# mcu_stm32f4.net
KiCad netlist of a schematic drawn in Altium Designer
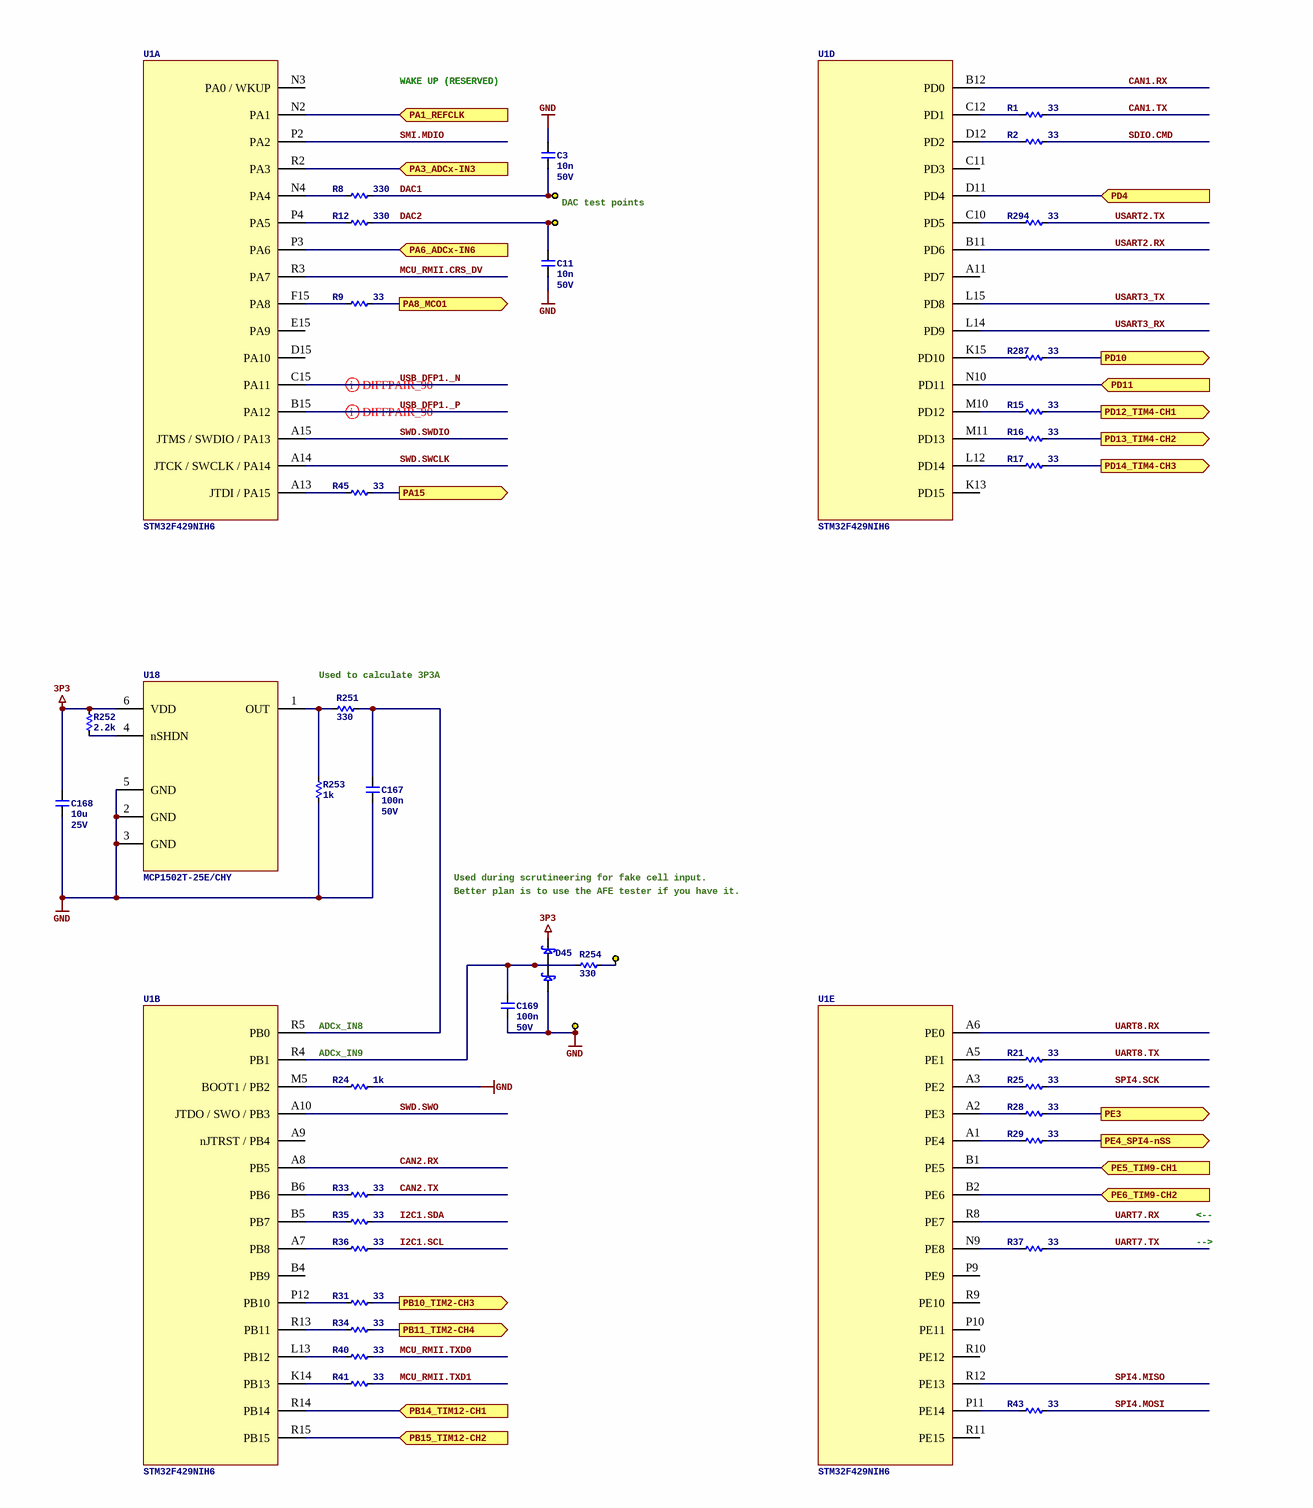
[diagram p0: mcu_stm32f4.SchDoc, top left]
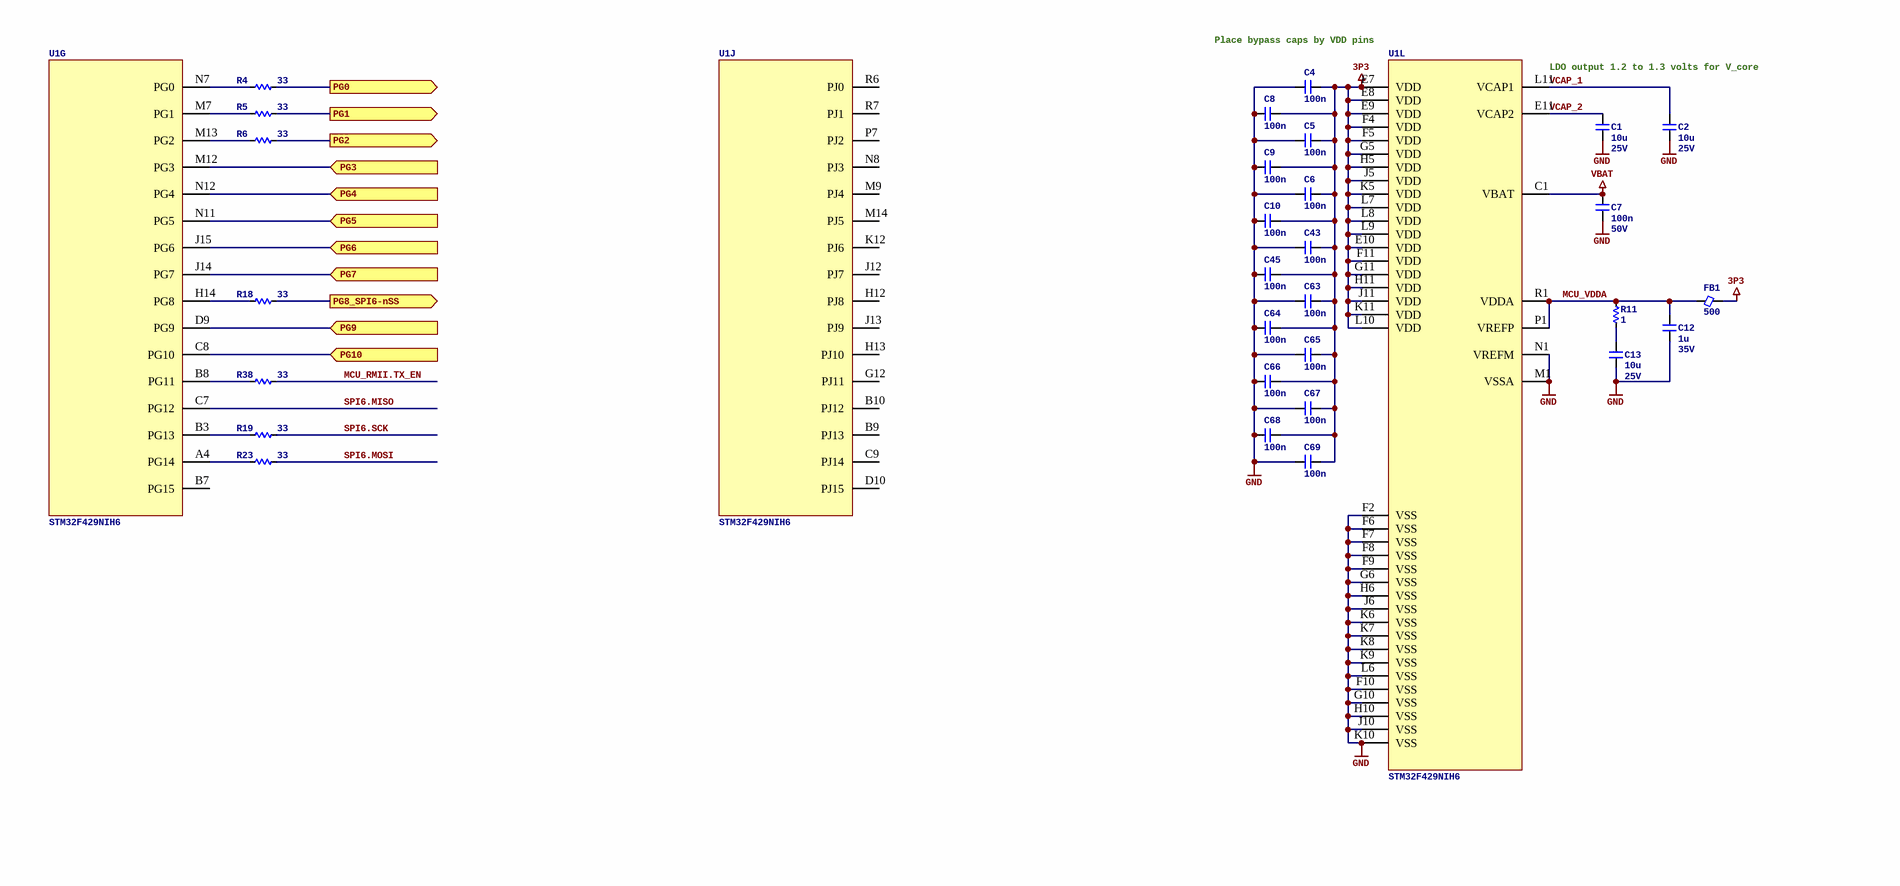
[diagram p1: mcu_stm32f4.SchDoc, top right]
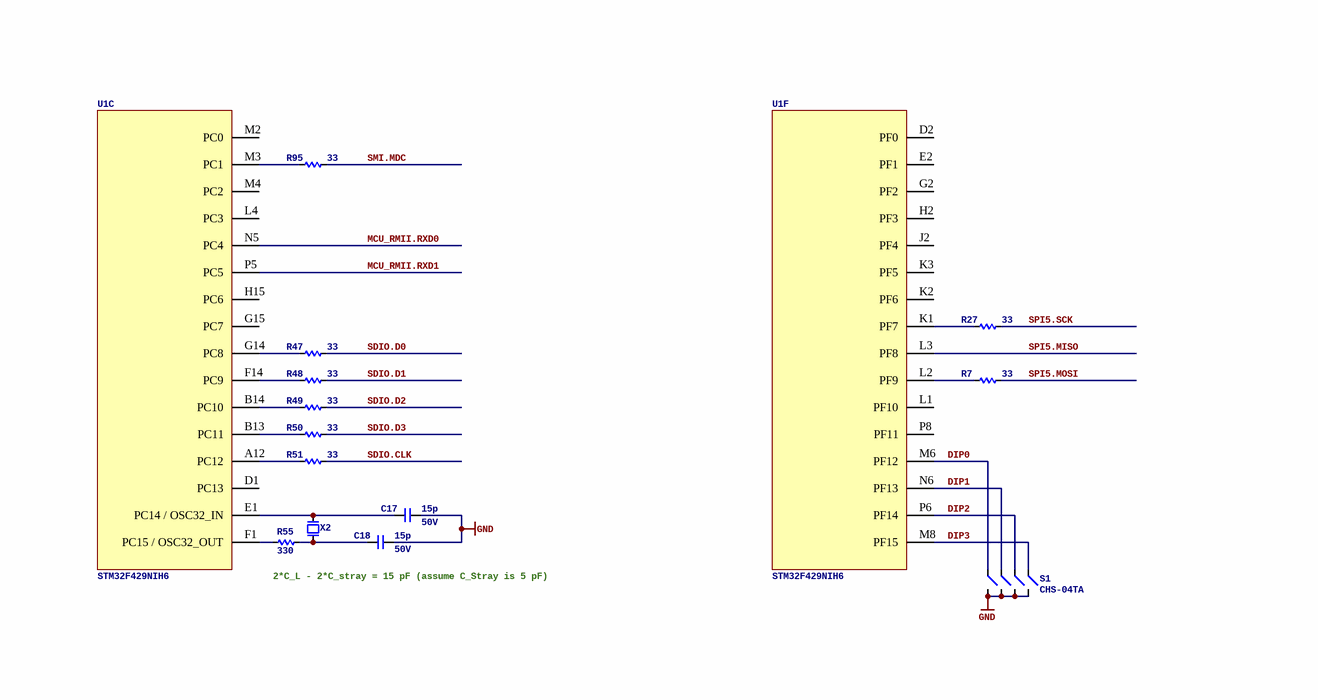
[diagram p2: mcu_stm32f4.SchDoc, bottom left]
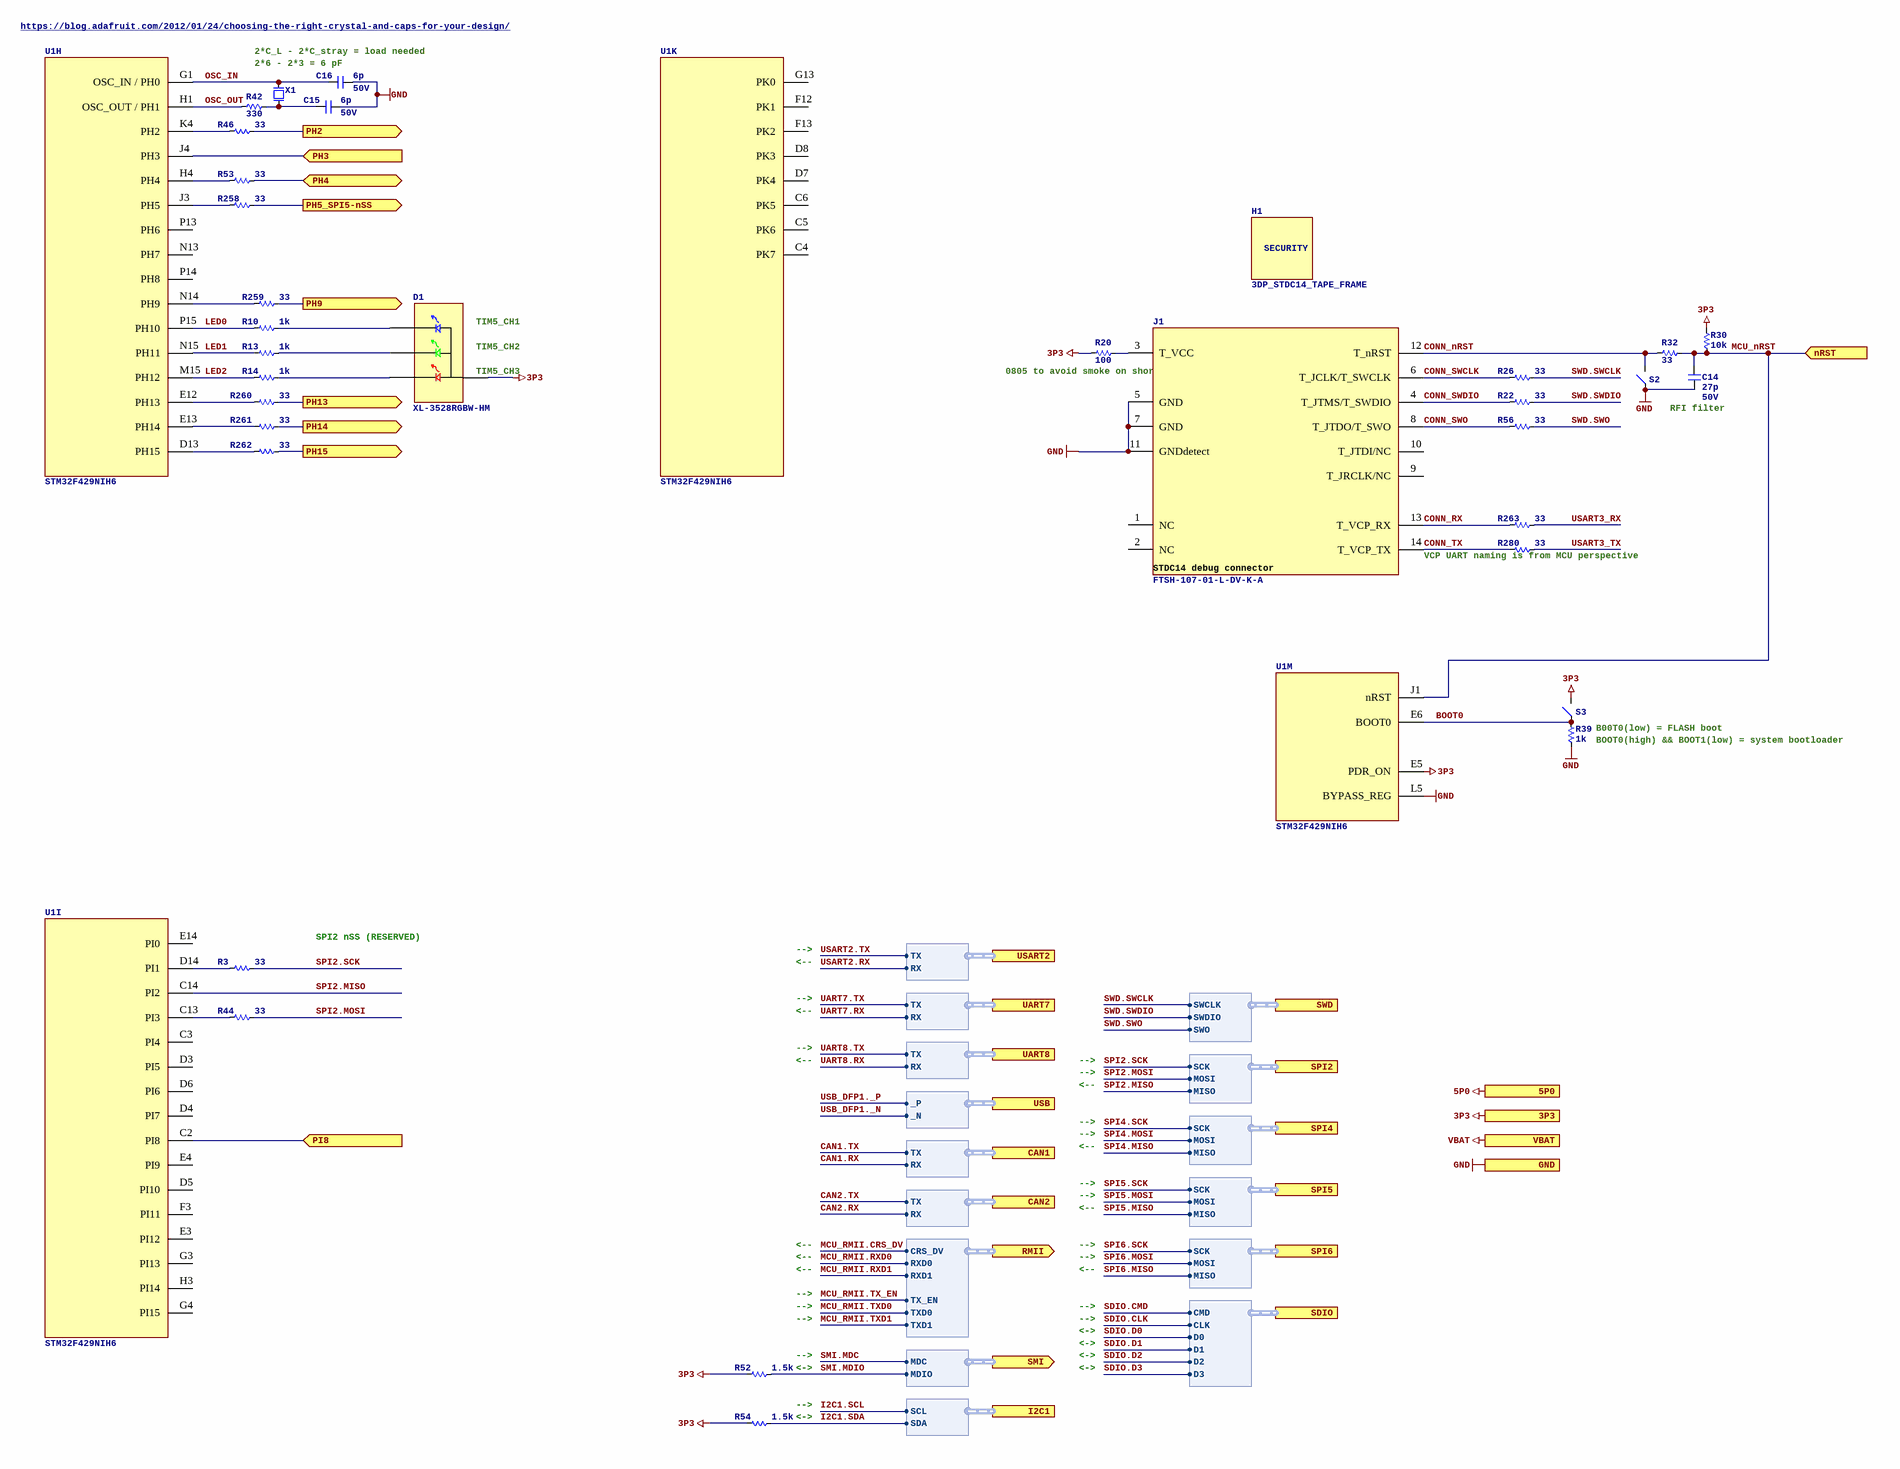
[diagram p3: mcu_stm32f4.SchDoc, bottom right]

(export (version "E")
  (design (tool "Eeschema 10.0.6"))
  (components
    (comp (ref "C1")
      (value "CL10A106MA8NRNC")
      (footprint "C0603")
      (fields
        (field (name "CAPACITANCE") "10u")
        (field (name "MANUFACTURER") "Samsung Electro-Mechanics")
        (field (name "VOLTAGE RATING") "25V")
      )
      (libsource (lib "database") (part "__template_cap"))
    )
    (comp (ref "C2")
      (value "CL10A106MA8NRNC")
      (footprint "C0603")
      (fields
        (field (name "CAPACITANCE") "10u")
        (field (name "MANUFACTURER") "Samsung Electro-Mechanics")
        (field (name "VOLTAGE RATING") "25V")
      )
      (libsource (lib "database") (part "__template_cap"))
    )
    (comp (ref "C3")
      (value "CL05B103KB5NNNC")
      (footprint "C0402")
      (fields
        (field (name "CAPACITANCE") "10n")
        (field (name "MANUFACTURER") "Samsung Electro-Mechanics")
        (field (name "VOLTAGE RATING") "50V")
      )
      (libsource (lib "database") (part "__template_cap"))
    )
    (comp (ref "C4")
      (value "CL05B104KB54PNC")
      (footprint "C0402")
      (fields (field (name "CAPACITANCE") "100n") (field (name "MANUFACTURER") "Samsung Electro-Mechanics"))
      (libsource (lib "database") (part "__template_cap"))
    )
    (comp (ref "C5")
      (value "CL05B104KB54PNC")
      (footprint "C0402")
      (fields (field (name "CAPACITANCE") "100n") (field (name "MANUFACTURER") "Samsung Electro-Mechanics"))
      (libsource (lib "database") (part "__template_cap"))
    )
    (comp (ref "C6")
      (value "CL05B104KB54PNC")
      (footprint "C0402")
      (fields (field (name "CAPACITANCE") "100n") (field (name "MANUFACTURER") "Samsung Electro-Mechanics"))
      (libsource (lib "database") (part "__template_cap"))
    )
    (comp (ref "C7")
      (value "CL05B104KB54PNC")
      (footprint "C0402")
      (fields
        (field (name "CAPACITANCE") "100n")
        (field (name "MANUFACTURER") "Samsung Electro-Mechanics")
        (field (name "VOLTAGE RATING") "50V")
      )
      (libsource (lib "database") (part "__template_cap"))
    )
    (comp (ref "C8")
      (value "CL05B104KB54PNC")
      (footprint "C0402")
      (fields (field (name "CAPACITANCE") "100n") (field (name "MANUFACTURER") "Samsung Electro-Mechanics"))
      (libsource (lib "database") (part "__template_cap"))
    )
    (comp (ref "C9")
      (value "CL05B104KB54PNC")
      (footprint "C0402")
      (fields (field (name "CAPACITANCE") "100n") (field (name "MANUFACTURER") "Samsung Electro-Mechanics"))
      (libsource (lib "database") (part "__template_cap"))
    )
    (comp (ref "C10")
      (value "CL05B104KB54PNC")
      (footprint "C0402")
      (fields (field (name "CAPACITANCE") "100n") (field (name "MANUFACTURER") "Samsung Electro-Mechanics"))
      (libsource (lib "database") (part "__template_cap"))
    )
    (comp (ref "C11")
      (value "CL05B103KB5NNNC")
      (footprint "C0402")
      (fields
        (field (name "CAPACITANCE") "10n")
        (field (name "MANUFACTURER") "Samsung Electro-Mechanics")
        (field (name "VOLTAGE RATING") "50V")
      )
      (libsource (lib "database") (part "__template_cap"))
    )
    (comp (ref "C12")
      (value "GMK107AB7105KAHT")
      (footprint "C0603")
      (fields
        (field (name "CAPACITANCE") "1u")
        (field (name "MANUFACTURER") "Taiyo Yuden")
        (field (name "VOLTAGE RATING") "35V")
      )
      (libsource (lib "database") (part "__template_cap"))
    )
    (comp (ref "C13")
      (value "CL21B106KAYQNNE")
      (footprint "C0805")
      (fields
        (field (name "CAPACITANCE") "10u")
        (field (name "MANUFACTURER") "Samsung Electro-Mechanics")
        (field (name "VOLTAGE RATING") "25V")
      )
      (libsource (lib "database") (part "__template_cap"))
    )
    (comp (ref "C14")
      (value "0402CG270J500NT")
      (footprint "C0402")
      (fields
        (field (name "CAPACITANCE") "27p")
        (field (name "MANUFACTURER") "FH(Guangdong Fenghua Advanced Tech)")
        (field (name "VOLTAGE RATING") "50V")
      )
      (libsource (lib "database") (part "__template_cap"))
    )
    (comp (ref "C15")
      (value "0402CG6R0C500NT")
      (footprint "C0402")
      (fields
        (field (name "CAPACITANCE") "6p")
        (field (name "MANUFACTURER") "FH(Guangdong Fenghua Advanced Tech)")
        (field (name "VOLTAGE RATING") "50V")
      )
      (libsource (lib "database") (part "__template_cap"))
    )
    (comp (ref "C16")
      (value "0402CG6R0C500NT")
      (footprint "C0402")
      (fields
        (field (name "CAPACITANCE") "6p")
        (field (name "MANUFACTURER") "FH(Guangdong Fenghua Advanced Tech)")
        (field (name "VOLTAGE RATING") "50V")
      )
      (libsource (lib "database") (part "__template_cap"))
    )
    (comp (ref "C17")
      (value "0402CG150J500NT")
      (footprint "C0402")
      (fields
        (field (name "CAPACITANCE") "15p")
        (field (name "MANUFACTURER") "FH(Guangdong Fenghua Advanced Tech)")
        (field (name "VOLTAGE RATING") "50V")
      )
      (libsource (lib "database") (part "__template_cap"))
    )
    (comp (ref "C18")
      (value "0402CG150J500NT")
      (footprint "C0402")
      (fields
        (field (name "CAPACITANCE") "15p")
        (field (name "MANUFACTURER") "FH(Guangdong Fenghua Advanced Tech)")
        (field (name "VOLTAGE RATING") "50V")
      )
      (libsource (lib "database") (part "__template_cap"))
    )
    (comp (ref "C43")
      (value "CL05B104KB54PNC")
      (footprint "C0402")
      (fields (field (name "CAPACITANCE") "100n") (field (name "MANUFACTURER") "Samsung Electro-Mechanics"))
      (libsource (lib "database") (part "__template_cap"))
    )
    (comp (ref "C45")
      (value "CL05B104KB54PNC")
      (footprint "C0402")
      (fields (field (name "CAPACITANCE") "100n") (field (name "MANUFACTURER") "Samsung Electro-Mechanics"))
      (libsource (lib "database") (part "__template_cap"))
    )
    (comp (ref "C63")
      (value "CL05B104KB54PNC")
      (footprint "C0402")
      (fields (field (name "CAPACITANCE") "100n") (field (name "MANUFACTURER") "Samsung Electro-Mechanics"))
      (libsource (lib "database") (part "__template_cap"))
    )
    (comp (ref "C64")
      (value "CL05B104KB54PNC")
      (footprint "C0402")
      (fields (field (name "CAPACITANCE") "100n") (field (name "MANUFACTURER") "Samsung Electro-Mechanics"))
      (libsource (lib "database") (part "__template_cap"))
    )
    (comp (ref "C65")
      (value "CL05B104KB54PNC")
      (footprint "C0402")
      (fields (field (name "CAPACITANCE") "100n") (field (name "MANUFACTURER") "Samsung Electro-Mechanics"))
      (libsource (lib "database") (part "__template_cap"))
    )
    (comp (ref "C66")
      (value "CL05B104KB54PNC")
      (footprint "C0402")
      (fields (field (name "CAPACITANCE") "100n") (field (name "MANUFACTURER") "Samsung Electro-Mechanics"))
      (libsource (lib "database") (part "__template_cap"))
    )
    (comp (ref "C67")
      (value "CL05B104KB54PNC")
      (footprint "C0402")
      (fields (field (name "CAPACITANCE") "100n") (field (name "MANUFACTURER") "Samsung Electro-Mechanics"))
      (libsource (lib "database") (part "__template_cap"))
    )
    (comp (ref "C68")
      (value "CL05B104KB54PNC")
      (footprint "C0402")
      (fields (field (name "CAPACITANCE") "100n") (field (name "MANUFACTURER") "Samsung Electro-Mechanics"))
      (libsource (lib "database") (part "__template_cap"))
    )
    (comp (ref "C69")
      (value "CL05B104KB54PNC")
      (footprint "C0402")
      (fields (field (name "CAPACITANCE") "100n") (field (name "MANUFACTURER") "Samsung Electro-Mechanics"))
      (libsource (lib "database") (part "__template_cap"))
    )
    (comp (ref "C167")
      (value "CL05B104KB54PNC")
      (footprint "C0402")
      (fields
        (field (name "CAPACITANCE") "100n")
        (field (name "MANUFACTURER") "Samsung Electro-Mechanics")
        (field (name "VOLTAGE RATING") "50V")
      )
      (libsource (lib "database") (part "__template_cap"))
    )
    (comp (ref "C168")
      (value "CL10A106MA8NRNC")
      (footprint "C0603")
      (fields
        (field (name "CAPACITANCE") "10u")
        (field (name "MANUFACTURER") "Samsung Electro-Mechanics")
        (field (name "VOLTAGE RATING") "25V")
      )
      (libsource (lib "database") (part "__template_cap"))
    )
    (comp (ref "C169")
      (value "CL05B104KB54PNC")
      (footprint "C0402")
      (fields
        (field (name "CAPACITANCE") "100n")
        (field (name "MANUFACTURER") "Samsung Electro-Mechanics")
        (field (name "VOLTAGE RATING") "50V")
      )
      (libsource (lib "database") (part "__template_cap"))
    )
    (comp (ref "D1")
      (value "XL-3528RGBW-HM")
      (footprint "LED_RGB_SMD3528-4P")
      (description "LED Multi-Color Chip Red/Green/Blue 621nm/525nm/468nm 25mA/15mA/15mA 4-Pin PLCC T/R")
      (fields (field (name "MANUFACTURER") "XINGLIGHT"))
      (libsource (lib "SSCP") (part "LED_RGB_XL-3528RGBW-HM"))
    )
    (comp (ref "D45")
      (value "BAT54SLT1G")
      (footprint "3SOT23")
      (description "DIODE SCHOTTKY DUAL 30V SOT23")
      (fields (field (name "MANUFACTURER") "ON Semiconductor"))
      (libsource (lib "SSCP") (part "SCHOTTKY_30V_DUAL_BAT54SLT1G"))
    )
    (comp (ref "FB1")
      (value "BLM15AX601SN1D")
      (footprint "FB0402")
      (fields (field (name "MANUFACTURER") "Murata Electronics") (field (name "CURRENT RATING (MA)") "500"))
      (libsource (lib "database") (part "__template_fb"))
    )
    (comp (ref "H1")
      (value "3DP_STDC14_TAPE_FRAME")
      (footprint "3DP_STDC14_TAPE_FRAME")
      (description "3D-printed plastic frame used for security tape around STDC14 programming header")
      (fields (field (name "MANUFACTURER") "SSCP"))
      (libsource (lib "SSCP") (part "3DP_STDC14_TAPE_FRAME"))
    )
    (comp (ref "J1")
      (value "FTSH-107-01-L-DV-K-A")
      (footprint "SAMTEC_FTSH-107-01-L-DV-K-A")
      (description "Connector Header Surface Mount 14 position 0.050\" (1.27mm)")
      (fields (field (name "MANUFACTURER") "Samtec"))
      (libsource (lib "SSCP") (part "CONN_14POS_50MIL_ST_CORTEX_DEBUG_VCP"))
    )
    (comp (ref "R1")
      (value "33")
      (footprint "R0402")
      (fields
        (field (name "TOLERANCE") "1%")
        (field (name "MANUFACTURER PART NUMBER") "0402WGF330JTCE")
        (field (name "MANUFACTURER") "UNI-ROYAL(Uniroyal Elec)")
      )
      (libsource (lib "database") (part "__template_resistor"))
    )
    (comp (ref "R2")
      (value "33")
      (footprint "R0402")
      (fields
        (field (name "TOLERANCE") "1%")
        (field (name "MANUFACTURER PART NUMBER") "0402WGF330JTCE")
        (field (name "MANUFACTURER") "UNI-ROYAL(Uniroyal Elec)")
      )
      (libsource (lib "database") (part "__template_resistor"))
    )
    (comp (ref "R3")
      (value "33")
      (footprint "R0402")
      (fields
        (field (name "TOLERANCE") "1%")
        (field (name "MANUFACTURER PART NUMBER") "0402WGF330JTCE")
        (field (name "MANUFACTURER") "UNI-ROYAL(Uniroyal Elec)")
      )
      (libsource (lib "database") (part "__template_resistor"))
    )
    (comp (ref "R4")
      (value "33")
      (footprint "R0402")
      (fields
        (field (name "TOLERANCE") "1%")
        (field (name "MANUFACTURER PART NUMBER") "0402WGF330JTCE")
        (field (name "MANUFACTURER") "UNI-ROYAL(Uniroyal Elec)")
      )
      (libsource (lib "database") (part "__template_resistor"))
    )
    (comp (ref "R5")
      (value "33")
      (footprint "R0402")
      (fields
        (field (name "TOLERANCE") "1%")
        (field (name "MANUFACTURER PART NUMBER") "0402WGF330JTCE")
        (field (name "MANUFACTURER") "UNI-ROYAL(Uniroyal Elec)")
      )
      (libsource (lib "database") (part "__template_resistor"))
    )
    (comp (ref "R6")
      (value "33")
      (footprint "R0402")
      (fields
        (field (name "TOLERANCE") "1%")
        (field (name "MANUFACTURER PART NUMBER") "0402WGF330JTCE")
        (field (name "MANUFACTURER") "UNI-ROYAL(Uniroyal Elec)")
      )
      (libsource (lib "database") (part "__template_resistor"))
    )
    (comp (ref "R7")
      (value "33")
      (footprint "R0402")
      (fields
        (field (name "TOLERANCE") "1%")
        (field (name "MANUFACTURER PART NUMBER") "0402WGF330JTCE")
        (field (name "MANUFACTURER") "UNI-ROYAL(Uniroyal Elec)")
      )
      (libsource (lib "database") (part "__template_resistor"))
    )
    (comp (ref "R8")
      (value "330")
      (footprint "R0402")
      (fields
        (field (name "TOLERANCE") "1%")
        (field (name "MANUFACTURER PART NUMBER") "0402WGF3300TCE")
        (field (name "MANUFACTURER") "UNI-ROYAL(Uniroyal Elec)")
      )
      (libsource (lib "database") (part "__template_resistor"))
    )
    (comp (ref "R9")
      (value "33")
      (footprint "R0402")
      (fields
        (field (name "TOLERANCE") "1%")
        (field (name "MANUFACTURER PART NUMBER") "0402WGF330JTCE")
        (field (name "MANUFACTURER") "UNI-ROYAL(Uniroyal Elec)")
      )
      (libsource (lib "database") (part "__template_resistor"))
    )
    (comp (ref "R10")
      (value "1k")
      (footprint "R0402")
      (fields
        (field (name "TOLERANCE") "1%")
        (field (name "MANUFACTURER PART NUMBER") "0402WGF1001TCE")
        (field (name "MANUFACTURER") "UNI-ROYAL(Uniroyal Elec)")
      )
      (libsource (lib "database") (part "__template_resistor"))
    )
    (comp (ref "R11")
      (value "1")
      (footprint "R0402")
      (fields
        (field (name "TOLERANCE") "1%")
        (field (name "MANUFACTURER PART NUMBER") "CRCW04021R00FKED")
        (field (name "MANUFACTURER") "Vishay Intertech")
      )
      (libsource (lib "database") (part "__template_resistor"))
    )
    (comp (ref "R12")
      (value "330")
      (footprint "R0402")
      (fields
        (field (name "TOLERANCE") "1%")
        (field (name "MANUFACTURER PART NUMBER") "0402WGF3300TCE")
        (field (name "MANUFACTURER") "UNI-ROYAL(Uniroyal Elec)")
      )
      (libsource (lib "database") (part "__template_resistor"))
    )
    (comp (ref "R13")
      (value "1k")
      (footprint "R0402")
      (fields
        (field (name "TOLERANCE") "1%")
        (field (name "MANUFACTURER PART NUMBER") "0402WGF1001TCE")
        (field (name "MANUFACTURER") "UNI-ROYAL(Uniroyal Elec)")
      )
      (libsource (lib "database") (part "__template_resistor"))
    )
    (comp (ref "R14")
      (value "1k")
      (footprint "R0402")
      (fields
        (field (name "TOLERANCE") "1%")
        (field (name "MANUFACTURER PART NUMBER") "0402WGF1001TCE")
        (field (name "MANUFACTURER") "UNI-ROYAL(Uniroyal Elec)")
      )
      (libsource (lib "database") (part "__template_resistor"))
    )
    (comp (ref "R15")
      (value "33")
      (footprint "R0402")
      (fields
        (field (name "TOLERANCE") "1%")
        (field (name "MANUFACTURER PART NUMBER") "0402WGF330JTCE")
        (field (name "MANUFACTURER") "UNI-ROYAL(Uniroyal Elec)")
      )
      (libsource (lib "database") (part "__template_resistor"))
    )
    (comp (ref "R16")
      (value "33")
      (footprint "R0402")
      (fields
        (field (name "TOLERANCE") "1%")
        (field (name "MANUFACTURER PART NUMBER") "0402WGF330JTCE")
        (field (name "MANUFACTURER") "UNI-ROYAL(Uniroyal Elec)")
      )
      (libsource (lib "database") (part "__template_resistor"))
    )
    (comp (ref "R17")
      (value "33")
      (footprint "R0402")
      (fields
        (field (name "TOLERANCE") "1%")
        (field (name "MANUFACTURER PART NUMBER") "0402WGF330JTCE")
        (field (name "MANUFACTURER") "UNI-ROYAL(Uniroyal Elec)")
      )
      (libsource (lib "database") (part "__template_resistor"))
    )
    (comp (ref "R18")
      (value "33")
      (footprint "R0402")
      (fields
        (field (name "TOLERANCE") "1%")
        (field (name "MANUFACTURER PART NUMBER") "0402WGF330JTCE")
        (field (name "MANUFACTURER") "UNI-ROYAL(Uniroyal Elec)")
      )
      (libsource (lib "database") (part "__template_resistor"))
    )
    (comp (ref "R19")
      (value "33")
      (footprint "R0402")
      (fields
        (field (name "TOLERANCE") "1%")
        (field (name "MANUFACTURER PART NUMBER") "0402WGF330JTCE")
        (field (name "MANUFACTURER") "UNI-ROYAL(Uniroyal Elec)")
      )
      (libsource (lib "database") (part "__template_resistor"))
    )
    (comp (ref "R20")
      (value "100")
      (footprint "R0805")
      (fields
        (field (name "TOLERANCE") "1%")
        (field (name "MANUFACTURER PART NUMBER") "ERJP06F1000V")
        (field (name "MANUFACTURER") "PANASONIC")
      )
      (libsource (lib "database") (part "__template_resistor"))
    )
    (comp (ref "R21")
      (value "33")
      (footprint "R0402")
      (fields
        (field (name "TOLERANCE") "1%")
        (field (name "MANUFACTURER PART NUMBER") "0402WGF330JTCE")
        (field (name "MANUFACTURER") "UNI-ROYAL(Uniroyal Elec)")
      )
      (libsource (lib "database") (part "__template_resistor"))
    )
    (comp (ref "R22")
      (value "33")
      (footprint "R0402")
      (fields
        (field (name "TOLERANCE") "1%")
        (field (name "MANUFACTURER PART NUMBER") "0402WGF330JTCE")
        (field (name "MANUFACTURER") "UNI-ROYAL(Uniroyal Elec)")
      )
      (libsource (lib "database") (part "__template_resistor"))
    )
    (comp (ref "R23")
      (value "33")
      (footprint "R0402")
      (fields
        (field (name "TOLERANCE") "1%")
        (field (name "MANUFACTURER PART NUMBER") "0402WGF330JTCE")
        (field (name "MANUFACTURER") "UNI-ROYAL(Uniroyal Elec)")
      )
      (libsource (lib "database") (part "__template_resistor"))
    )
    (comp (ref "R24")
      (value "1k")
      (footprint "R0402")
      (fields
        (field (name "TOLERANCE") "1%")
        (field (name "MANUFACTURER PART NUMBER") "0402WGF1001TCE")
        (field (name "MANUFACTURER") "UNI-ROYAL(Uniroyal Elec)")
      )
      (libsource (lib "database") (part "__template_resistor"))
    )
    (comp (ref "R25")
      (value "33")
      (footprint "R0402")
      (fields
        (field (name "TOLERANCE") "1%")
        (field (name "MANUFACTURER PART NUMBER") "0402WGF330JTCE")
        (field (name "MANUFACTURER") "UNI-ROYAL(Uniroyal Elec)")
      )
      (libsource (lib "database") (part "__template_resistor"))
    )
    (comp (ref "R26")
      (value "33")
      (footprint "R0402")
      (fields
        (field (name "TOLERANCE") "1%")
        (field (name "MANUFACTURER PART NUMBER") "0402WGF330JTCE")
        (field (name "MANUFACTURER") "UNI-ROYAL(Uniroyal Elec)")
      )
      (libsource (lib "database") (part "__template_resistor"))
    )
    (comp (ref "R27")
      (value "33")
      (footprint "R0402")
      (fields
        (field (name "TOLERANCE") "1%")
        (field (name "MANUFACTURER PART NUMBER") "0402WGF330JTCE")
        (field (name "MANUFACTURER") "UNI-ROYAL(Uniroyal Elec)")
      )
      (libsource (lib "database") (part "__template_resistor"))
    )
    (comp (ref "R28")
      (value "33")
      (footprint "R0402")
      (fields
        (field (name "TOLERANCE") "1%")
        (field (name "MANUFACTURER PART NUMBER") "0402WGF330JTCE")
        (field (name "MANUFACTURER") "UNI-ROYAL(Uniroyal Elec)")
      )
      (libsource (lib "database") (part "__template_resistor"))
    )
    (comp (ref "R29")
      (value "33")
      (footprint "R0402")
      (fields
        (field (name "TOLERANCE") "1%")
        (field (name "MANUFACTURER PART NUMBER") "0402WGF330JTCE")
        (field (name "MANUFACTURER") "UNI-ROYAL(Uniroyal Elec)")
      )
      (libsource (lib "database") (part "__template_resistor"))
    )
    (comp (ref "R30")
      (value "10k")
      (footprint "R0402")
      (fields
        (field (name "TOLERANCE") "1%")
        (field (name "MANUFACTURER PART NUMBER") "0402WGF1002TCE")
        (field (name "MANUFACTURER") "UNI-ROYAL(Uniroyal Elec)")
      )
      (libsource (lib "database") (part "__template_resistor"))
    )
    (comp (ref "R31")
      (value "33")
      (footprint "R0402")
      (fields
        (field (name "TOLERANCE") "1%")
        (field (name "MANUFACTURER PART NUMBER") "0402WGF330JTCE")
        (field (name "MANUFACTURER") "UNI-ROYAL(Uniroyal Elec)")
      )
      (libsource (lib "database") (part "__template_resistor"))
    )
    (comp (ref "R32")
      (value "33")
      (footprint "R0402")
      (fields
        (field (name "TOLERANCE") "1%")
        (field (name "MANUFACTURER PART NUMBER") "0402WGF330JTCE")
        (field (name "MANUFACTURER") "UNI-ROYAL(Uniroyal Elec)")
      )
      (libsource (lib "database") (part "__template_resistor"))
    )
    (comp (ref "R33")
      (value "33")
      (footprint "R0402")
      (fields
        (field (name "TOLERANCE") "1%")
        (field (name "MANUFACTURER PART NUMBER") "0402WGF330JTCE")
        (field (name "MANUFACTURER") "UNI-ROYAL(Uniroyal Elec)")
      )
      (libsource (lib "database") (part "__template_resistor"))
    )
    (comp (ref "R34")
      (value "33")
      (footprint "R0402")
      (fields
        (field (name "TOLERANCE") "1%")
        (field (name "MANUFACTURER PART NUMBER") "0402WGF330JTCE")
        (field (name "MANUFACTURER") "UNI-ROYAL(Uniroyal Elec)")
      )
      (libsource (lib "database") (part "__template_resistor"))
    )
    (comp (ref "R35")
      (value "33")
      (footprint "R0402")
      (fields
        (field (name "TOLERANCE") "1%")
        (field (name "MANUFACTURER PART NUMBER") "0402WGF330JTCE")
        (field (name "MANUFACTURER") "UNI-ROYAL(Uniroyal Elec)")
      )
      (libsource (lib "database") (part "__template_resistor"))
    )
    (comp (ref "R36")
      (value "33")
      (footprint "R0402")
      (fields
        (field (name "TOLERANCE") "1%")
        (field (name "MANUFACTURER PART NUMBER") "0402WGF330JTCE")
        (field (name "MANUFACTURER") "UNI-ROYAL(Uniroyal Elec)")
      )
      (libsource (lib "database") (part "__template_resistor"))
    )
    (comp (ref "R37")
      (value "33")
      (footprint "R0402")
      (fields
        (field (name "TOLERANCE") "1%")
        (field (name "MANUFACTURER PART NUMBER") "0402WGF330JTCE")
        (field (name "MANUFACTURER") "UNI-ROYAL(Uniroyal Elec)")
      )
      (libsource (lib "database") (part "__template_resistor"))
    )
    (comp (ref "R38")
      (value "33")
      (footprint "R0402")
      (fields
        (field (name "TOLERANCE") "1%")
        (field (name "MANUFACTURER PART NUMBER") "0402WGF330JTCE")
        (field (name "MANUFACTURER") "UNI-ROYAL(Uniroyal Elec)")
      )
      (libsource (lib "database") (part "__template_resistor"))
    )
    (comp (ref "R39")
      (value "1k")
      (footprint "R0402")
      (fields
        (field (name "TOLERANCE") "1%")
        (field (name "MANUFACTURER PART NUMBER") "0402WGF1001TCE")
        (field (name "MANUFACTURER") "UNI-ROYAL(Uniroyal Elec)")
      )
      (libsource (lib "database") (part "__template_resistor"))
    )
    (comp (ref "R40")
      (value "33")
      (footprint "R0402")
      (fields
        (field (name "TOLERANCE") "1%")
        (field (name "MANUFACTURER PART NUMBER") "0402WGF330JTCE")
        (field (name "MANUFACTURER") "UNI-ROYAL(Uniroyal Elec)")
      )
      (libsource (lib "database") (part "__template_resistor"))
    )
    (comp (ref "R41")
      (value "33")
      (footprint "R0402")
      (fields
        (field (name "TOLERANCE") "1%")
        (field (name "MANUFACTURER PART NUMBER") "0402WGF330JTCE")
        (field (name "MANUFACTURER") "UNI-ROYAL(Uniroyal Elec)")
      )
      (libsource (lib "database") (part "__template_resistor"))
    )
    (comp (ref "R42")
      (value "330")
      (footprint "R0402")
      (fields
        (field (name "TOLERANCE") "1%")
        (field (name "MANUFACTURER PART NUMBER") "0402WGF3300TCE")
        (field (name "MANUFACTURER") "UNI-ROYAL(Uniroyal Elec)")
      )
      (libsource (lib "database") (part "__template_resistor"))
    )
    (comp (ref "R43")
      (value "33")
      (footprint "R0402")
      (fields
        (field (name "TOLERANCE") "1%")
        (field (name "MANUFACTURER PART NUMBER") "0402WGF330JTCE")
        (field (name "MANUFACTURER") "UNI-ROYAL(Uniroyal Elec)")
      )
      (libsource (lib "database") (part "__template_resistor"))
    )
    (comp (ref "R44")
      (value "33")
      (footprint "R0402")
      (fields
        (field (name "TOLERANCE") "1%")
        (field (name "MANUFACTURER PART NUMBER") "0402WGF330JTCE")
        (field (name "MANUFACTURER") "UNI-ROYAL(Uniroyal Elec)")
      )
      (libsource (lib "database") (part "__template_resistor"))
    )
    (comp (ref "R45")
      (value "33")
      (footprint "R0402")
      (fields
        (field (name "TOLERANCE") "1%")
        (field (name "MANUFACTURER PART NUMBER") "0402WGF330JTCE")
        (field (name "MANUFACTURER") "UNI-ROYAL(Uniroyal Elec)")
      )
      (libsource (lib "database") (part "__template_resistor"))
    )
    (comp (ref "R46")
      (value "33")
      (footprint "R0402")
      (fields
        (field (name "TOLERANCE") "1%")
        (field (name "MANUFACTURER PART NUMBER") "0402WGF330JTCE")
        (field (name "MANUFACTURER") "UNI-ROYAL(Uniroyal Elec)")
      )
      (libsource (lib "database") (part "__template_resistor"))
    )
    (comp (ref "R47")
      (value "33")
      (footprint "R0402")
      (fields
        (field (name "TOLERANCE") "1%")
        (field (name "MANUFACTURER PART NUMBER") "0402WGF330JTCE")
        (field (name "MANUFACTURER") "UNI-ROYAL(Uniroyal Elec)")
      )
      (libsource (lib "database") (part "__template_resistor"))
    )
    (comp (ref "R48")
      (value "33")
      (footprint "R0402")
      (fields
        (field (name "TOLERANCE") "1%")
        (field (name "MANUFACTURER PART NUMBER") "0402WGF330JTCE")
        (field (name "MANUFACTURER") "UNI-ROYAL(Uniroyal Elec)")
      )
      (libsource (lib "database") (part "__template_resistor"))
    )
    (comp (ref "R49")
      (value "33")
      (footprint "R0402")
      (fields
        (field (name "TOLERANCE") "1%")
        (field (name "MANUFACTURER PART NUMBER") "0402WGF330JTCE")
        (field (name "MANUFACTURER") "UNI-ROYAL(Uniroyal Elec)")
      )
      (libsource (lib "database") (part "__template_resistor"))
    )
    (comp (ref "R50")
      (value "33")
      (footprint "R0402")
      (fields
        (field (name "TOLERANCE") "1%")
        (field (name "MANUFACTURER PART NUMBER") "0402WGF330JTCE")
        (field (name "MANUFACTURER") "UNI-ROYAL(Uniroyal Elec)")
      )
      (libsource (lib "database") (part "__template_resistor"))
    )
    (comp (ref "R51")
      (value "33")
      (footprint "R0402")
      (fields
        (field (name "TOLERANCE") "1%")
        (field (name "MANUFACTURER PART NUMBER") "0402WGF330JTCE")
        (field (name "MANUFACTURER") "UNI-ROYAL(Uniroyal Elec)")
      )
      (libsource (lib "database") (part "__template_resistor"))
    )
    (comp (ref "R52")
      (value "1.5k")
      (footprint "R0402")
      (fields
        (field (name "TOLERANCE") "1%")
        (field (name "MANUFACTURER PART NUMBER") "0402WGF1501TCE")
        (field (name "MANUFACTURER") "UNI-ROYAL(Uniroyal Elec)")
      )
      (libsource (lib "database") (part "__template_resistor"))
    )
    (comp (ref "R53")
      (value "33")
      (footprint "R0402")
      (fields
        (field (name "TOLERANCE") "1%")
        (field (name "MANUFACTURER PART NUMBER") "0402WGF330JTCE")
        (field (name "MANUFACTURER") "UNI-ROYAL(Uniroyal Elec)")
      )
      (libsource (lib "database") (part "__template_resistor"))
    )
    (comp (ref "R54")
      (value "1.5k")
      (footprint "R0402")
      (fields
        (field (name "TOLERANCE") "1%")
        (field (name "MANUFACTURER PART NUMBER") "0402WGF1501TCE")
        (field (name "MANUFACTURER") "UNI-ROYAL(Uniroyal Elec)")
      )
      (libsource (lib "database") (part "__template_resistor"))
    )
    (comp (ref "R55")
      (value "330")
      (footprint "R0402")
      (fields
        (field (name "TOLERANCE") "1%")
        (field (name "MANUFACTURER PART NUMBER") "0402WGF3300TCE")
        (field (name "MANUFACTURER") "UNI-ROYAL(Uniroyal Elec)")
      )
      (libsource (lib "database") (part "__template_resistor"))
    )
    (comp (ref "R56")
      (value "33")
      (footprint "R0402")
      (fields
        (field (name "TOLERANCE") "1%")
        (field (name "MANUFACTURER PART NUMBER") "0402WGF330JTCE")
        (field (name "MANUFACTURER") "UNI-ROYAL(Uniroyal Elec)")
      )
      (libsource (lib "database") (part "__template_resistor"))
    )
    (comp (ref "R95")
      (value "33")
      (footprint "R0402")
      (fields
        (field (name "TOLERANCE") "1%")
        (field (name "MANUFACTURER PART NUMBER") "0402WGF330JTCE")
        (field (name "MANUFACTURER") "UNI-ROYAL(Uniroyal Elec)")
      )
      (libsource (lib "database") (part "__template_resistor"))
    )
    (comp (ref "R251")
      (value "330")
      (footprint "R0402")
      (fields
        (field (name "TOLERANCE") "1%")
        (field (name "MANUFACTURER PART NUMBER") "0402WGF3300TCE")
        (field (name "MANUFACTURER") "UNI-ROYAL(Uniroyal Elec)")
      )
      (libsource (lib "database") (part "__template_resistor"))
    )
    (comp (ref "R252")
      (value "2.2k")
      (footprint "R0402")
      (fields
        (field (name "TOLERANCE") "1%")
        (field (name "MANUFACTURER PART NUMBER") "0402WGF2201TCE")
        (field (name "MANUFACTURER") "UNI-ROYAL(Uniroyal Elec)")
      )
      (libsource (lib "database") (part "__template_resistor"))
    )
    (comp (ref "R253")
      (value "1k")
      (footprint "R0402")
      (fields
        (field (name "TOLERANCE") "1%")
        (field (name "MANUFACTURER PART NUMBER") "0402WGF1001TCE")
        (field (name "MANUFACTURER") "UNI-ROYAL(Uniroyal Elec)")
      )
      (libsource (lib "database") (part "__template_resistor"))
    )
    (comp (ref "R254")
      (value "330")
      (footprint "R0402")
      (fields
        (field (name "TOLERANCE") "1%")
        (field (name "MANUFACTURER PART NUMBER") "0402WGF3300TCE")
        (field (name "MANUFACTURER") "UNI-ROYAL(Uniroyal Elec)")
      )
      (libsource (lib "database") (part "__template_resistor"))
    )
    (comp (ref "R258")
      (value "33")
      (footprint "R0402")
      (fields
        (field (name "TOLERANCE") "1%")
        (field (name "MANUFACTURER PART NUMBER") "0402WGF330JTCE")
        (field (name "MANUFACTURER") "UNI-ROYAL(Uniroyal Elec)")
      )
      (libsource (lib "database") (part "__template_resistor"))
    )
    (comp (ref "R259")
      (value "33")
      (footprint "R0402")
      (fields
        (field (name "TOLERANCE") "1%")
        (field (name "MANUFACTURER PART NUMBER") "0402WGF330JTCE")
        (field (name "MANUFACTURER") "UNI-ROYAL(Uniroyal Elec)")
      )
      (libsource (lib "database") (part "__template_resistor"))
    )
    (comp (ref "R260")
      (value "33")
      (footprint "R0402")
      (fields
        (field (name "TOLERANCE") "1%")
        (field (name "MANUFACTURER PART NUMBER") "0402WGF330JTCE")
        (field (name "MANUFACTURER") "UNI-ROYAL(Uniroyal Elec)")
      )
      (libsource (lib "database") (part "__template_resistor"))
    )
    (comp (ref "R261")
      (value "33")
      (footprint "R0402")
      (fields
        (field (name "TOLERANCE") "1%")
        (field (name "MANUFACTURER PART NUMBER") "0402WGF330JTCE")
        (field (name "MANUFACTURER") "UNI-ROYAL(Uniroyal Elec)")
      )
      (libsource (lib "database") (part "__template_resistor"))
    )
    (comp (ref "R262")
      (value "33")
      (footprint "R0402")
      (fields
        (field (name "TOLERANCE") "1%")
        (field (name "MANUFACTURER PART NUMBER") "0402WGF330JTCE")
        (field (name "MANUFACTURER") "UNI-ROYAL(Uniroyal Elec)")
      )
      (libsource (lib "database") (part "__template_resistor"))
    )
    (comp (ref "R263")
      (value "33")
      (footprint "R0402")
      (fields
        (field (name "TOLERANCE") "1%")
        (field (name "MANUFACTURER PART NUMBER") "0402WGF330JTCE")
        (field (name "MANUFACTURER") "UNI-ROYAL(Uniroyal Elec)")
      )
      (libsource (lib "database") (part "__template_resistor"))
    )
    (comp (ref "R280")
      (value "33")
      (footprint "R0402")
      (fields
        (field (name "TOLERANCE") "1%")
        (field (name "MANUFACTURER PART NUMBER") "0402WGF330JTCE")
        (field (name "MANUFACTURER") "UNI-ROYAL(Uniroyal Elec)")
      )
      (libsource (lib "database") (part "__template_resistor"))
    )
    (comp (ref "R287")
      (value "33")
      (footprint "R0402")
      (fields
        (field (name "TOLERANCE") "1%")
        (field (name "MANUFACTURER PART NUMBER") "0402WGF330JTCE")
        (field (name "MANUFACTURER") "UNI-ROYAL(Uniroyal Elec)")
      )
      (libsource (lib "database") (part "__template_resistor"))
    )
    (comp (ref "R294")
      (value "33")
      (footprint "R0402")
      (fields
        (field (name "TOLERANCE") "1%")
        (field (name "MANUFACTURER PART NUMBER") "0402WGF330JTCE")
        (field (name "MANUFACTURER") "UNI-ROYAL(Uniroyal Elec)")
      )
      (libsource (lib "database") (part "__template_resistor"))
    )
    (comp (ref "S1")
      (value "CHS-04TA")
      (footprint "SWITCH_NIDEC_CHS-04TA")
      (description "DIP Switch, Slide, SPST, Flush, Recessed, 6VDC, 100mA, CHS Series ¦ Nidec Components CHS-04TA")
      (fields (field (name "MANUFACTURER") "Nidec Copal"))
      (libsource (lib "SSCP") (part "SWITCH_CHS-04TA"))
    )
    (comp (ref "S2")
      (value "TS-1092S-B3D2-G")
      (footprint "SWITCH_TS-1092S-B3D2-G")
      (description "SWITCH TACTILE SPST-NO")
      (fields (field (name "MANUFACTURER") "Yuandi"))
      (libsource (lib "SSCP") (part "SWITCH_TS-1092S-B3D2-G"))
    )
    (comp (ref "S3")
      (value "TS-1092S-B3D2-G")
      (footprint "SWITCH_TS-1092S-B3D2-G")
      (description "SWITCH TACTILE SPST-NO")
      (fields (field (name "MANUFACTURER") "Yuandi"))
      (libsource (lib "SSCP") (part "SWITCH_TS-1092S-B3D2-G"))
    )
    (comp (ref "TP1")
      (value "RH-5002")
      (footprint "TP_RH-5002")
      (fields (field (name "MANUFACTURER") "ronghe"))
      (libsource (lib "database") (part "__template_testpoint"))
    )
    (comp (ref "TP2")
      (value "RH-5002")
      (footprint "TP_RH-5002")
      (fields (field (name "MANUFACTURER") "ronghe"))
      (libsource (lib "database") (part "__template_testpoint"))
    )
    (comp (ref "TP51")
      (value "RH-5000")
      (footprint "TP_RH-5000")
      (fields (field (name "MANUFACTURER") "ronghe"))
      (libsource (lib "database") (part "__template_testpoint"))
    )
    (comp (ref "TP52")
      (value "RH-5001")
      (footprint "TP_RH-5001")
      (fields (field (name "MANUFACTURER") "ronghe"))
      (libsource (lib "database") (part "__template_testpoint"))
    )
    (comp (ref "U1")
      (value "STM32F429NIH6")
      (footprint "ST_TFBGA216")
      (description "ARM® Cortex®-M4 STM32F4 Microcontroller IC 32-Bit 180MHz 2MB (2M x 8) FLASH 216-TFBGA (13x13)")
      (fields (field (name "MANUFACTURER") "STMicroelectronics"))
      (libsource (lib "SSCP") (part "MCU_STM32F429NIH6"))
    )
    (comp (ref "U18")
      (value "MCP1502T-25E/CHY")
      (footprint "6SOT23")
      (description "IC 7 PPM 0.1% VOLTAGE REFERENCE Series Voltage Reference IC Fixed 2.5V V ±0.1% 20 mA SOT-23-6")
      (fields (field (name "MANUFACTURER") "Microchip"))
      (libsource (lib "SSCP") (part "REF_2.5V_MCP1502T-25E/CHY"))
    )
    (comp (ref "X1")
      (value "XTAL_XRCGB25M000F3A00R0")
      (footprint "4_SMD_2.0X1.6MM")
      (description "CRYSTAL 25.000MHZ 6PF SMD")
      (fields
        (field (name "MANUFACTURER") "Murata")
        (field (name "MANUFACTURER PART NUMBER") "XRCGB25M000F3A00R0")
      )
      (libsource (lib "SSCP") (part "XTAL_XRCGB25M000F3A00R0"))
    )
    (comp (ref "X2")
      (value "XTAL_9HT10-32.768KEZF-T")
      (footprint "XTAL_TXC_9HT10")
      (description "CRYSTAL 32.768 KHZ 12.5 PF SMD")
      (fields
        (field (name "MANUFACTURER") "TXC CORPORATION")
        (field (name "MANUFACTURER PART NUMBER") "9HT10-32.768KEZF-T")
      )
      (libsource (lib "SSCP") (part "XTAL_9HT10-32.768KEZF-T"))
    )
  )
  (nets
    (net (code "10") (name "/BOOT0") (class "Default")
      (node (ref "R39") (pin "1") (pintype "passive"))
      (node (ref "S3") (pin "1") (pintype "passive"))
      (node (ref "U1") (pin "E6") (pinfunction "BOOT0_E6") (pintype "passive"))
    )
    (net (code "11") (name "/CAN1.RX") (class "Default")
      (node (ref "U1") (pin "B12") (pinfunction "PD0_B12") (pintype "passive"))
    )
    (net (code "12") (name "/CAN1.TX") (class "Default") (node (ref "R1") (pin "1") (pintype "passive")))
    (net (code "13") (name "/CAN2.RX") (class "Default")
      (node (ref "U1") (pin "A8") (pinfunction "PB5_A8") (pintype "passive"))
    )
    (net (code "14") (name "/CAN2.TX") (class "Default") (node (ref "R33") (pin "1") (pintype "passive")))
    (net (code "15") (name "/CONN_RX") (class "Default")
      (node (ref "J1") (pin "13") (pinfunction "T_VCP_RX_13") (pintype "passive"))
      (node (ref "R263") (pin "2") (pintype "passive"))
    )
    (net (code "16") (name "/CONN_SWCLK") (class "Default")
      (node (ref "J1") (pin "6") (pinfunction "T_JCLK/T_SWCLK_6") (pintype "passive"))
      (node (ref "R26") (pin "2") (pintype "passive"))
    )
    (net (code "17") (name "/CONN_SWDIO") (class "Default")
      (node (ref "J1") (pin "4") (pinfunction "T_JTMS/T_SWDIO_4") (pintype "passive"))
      (node (ref "R22") (pin "2") (pintype "passive"))
    )
    (net (code "18") (name "/CONN_SWO") (class "Default")
      (node (ref "J1") (pin "8") (pinfunction "T_JTDO/T_SWO_8") (pintype "passive"))
      (node (ref "R56") (pin "2") (pintype "passive"))
    )
    (net (code "19") (name "/CONN_TX") (class "Default")
      (node (ref "J1") (pin "14") (pinfunction "T_VCP_TX_14") (pintype "passive"))
      (node (ref "R280") (pin "2") (pintype "passive"))
    )
    (net (code "20") (name "/CONN_nRST") (class "Default")
      (node (ref "J1") (pin "12") (pinfunction "T_nRST_12") (pintype "passive"))
      (node (ref "R32") (pin "2") (pintype "passive"))
      (node (ref "S2") (pin "2") (pintype "passive"))
    )
    (net (code "21") (name "/DAC1") (class "Default")
      (node (ref "C3") (pin "1") (pintype "passive"))
      (node (ref "R8") (pin "2") (pintype "passive"))
      (node (ref "TP1") (pin "1") (pintype "passive"))
    )
    (net (code "22") (name "/DAC2") (class "Default")
      (node (ref "C11") (pin "1") (pintype "passive"))
      (node (ref "R12") (pin "2") (pintype "passive"))
      (node (ref "TP2") (pin "1") (pintype "passive"))
    )
    (net (code "23") (name "/DIP0") (class "Default")
      (node (ref "S1") (pin "7") (pintype "passive"))
      (node (ref "U1") (pin "M6") (pinfunction "PF12_M6") (pintype "passive"))
    )
    (net (code "24") (name "/DIP1") (class "Default")
      (node (ref "S1") (pin "5") (pintype "passive"))
      (node (ref "U1") (pin "N6") (pinfunction "PF13_N6") (pintype "passive"))
    )
    (net (code "25") (name "/DIP2") (class "Default")
      (node (ref "S1") (pin "3") (pintype "passive"))
      (node (ref "U1") (pin "P6") (pinfunction "PF14_P6") (pintype "passive"))
    )
    (net (code "26") (name "/DIP3") (class "Default")
      (node (ref "S1") (pin "1") (pintype "passive"))
      (node (ref "U1") (pin "M8") (pinfunction "PF15_M8") (pintype "passive"))
    )
    (net (code "27") (name "/I2C1.SCL") (class "Default") (node (ref "R36") (pin "1") (pintype "passive")))
    (net (code "28") (name "/I2C1.SDA") (class "Default")
      (node (ref "R35") (pin "1") (pintype "passive"))
      (node (ref "R54") (pin "1") (pintype "passive"))
    )
    (net (code "29") (name "/LED0") (class "Default")
      (node (ref "R10") (pin "2") (pintype "passive"))
      (node (ref "U1") (pin "P15") (pinfunction "PH10_P15") (pintype "passive"))
    )
    (net (code "30") (name "/LED1") (class "Default")
      (node (ref "R13") (pin "2") (pintype "passive"))
      (node (ref "U1") (pin "N15") (pinfunction "PH11_N15") (pintype "passive"))
    )
    (net (code "31") (name "/LED2") (class "Default")
      (node (ref "R14") (pin "2") (pintype "passive"))
      (node (ref "U1") (pin "M15") (pinfunction "PH12_M15") (pintype "passive"))
    )
    (net (code "32") (name "/MCU_RMII.CRS_DV") (class "Default")
      (node (ref "U1") (pin "R3") (pinfunction "PA7_R3") (pintype "passive"))
    )
    (net (code "33") (name "/MCU_RMII.RXD0") (class "Default")
      (node (ref "U1") (pin "N5") (pinfunction "PC4_N5") (pintype "passive"))
    )
    (net (code "34") (name "/MCU_RMII.RXD1") (class "Default")
      (node (ref "U1") (pin "P5") (pinfunction "PC5_P5") (pintype "passive"))
    )
    (net (code "35") (name "/MCU_RMII.TXD0") (class "Default")
      (node (ref "R40") (pin "1") (pintype "passive"))
    )
    (net (code "36") (name "/MCU_RMII.TXD1") (class "Default")
      (node (ref "R41") (pin "1") (pintype "passive"))
    )
    (net (code "37") (name "/MCU_RMII.TX_EN") (class "Default")
      (node (ref "R38") (pin "1") (pintype "passive"))
    )
    (net (code "38") (name "/MCU_VDDA") (class "Default")
      (node (ref "C12") (pin "1") (pintype "passive"))
      (node (ref "FB1") (pin "1") (pintype "passive"))
      (node (ref "R11") (pin "2") (pintype "passive"))
      (node (ref "U1") (pin "P1") (pinfunction "VREFP_P1") (pintype "passive"))
      (node (ref "U1") (pin "R1") (pinfunction "VDDA_R1") (pintype "passive"))
    )
    (net (code "39") (name "/MCU_nRST") (class "Default")
      (node (ref "C14") (pin "1") (pintype "passive"))
      (node (ref "R30") (pin "2") (pintype "passive"))
      (node (ref "R32") (pin "1") (pintype "passive"))
      (node (ref "U1") (pin "J1") (pinfunction "nRST_J1") (pintype "passive"))
    )
    (net (code "40") (name "/OSC_IN") (class "Default")
      (node (ref "C16") (pin "1") (pintype "passive"))
      (node (ref "U1") (pin "G1") (pinfunction "OSC_IN_/_PH0_G1") (pintype "passive"))
      (node (ref "X1") (pin "3") (pinfunction "3_3") (pintype "passive"))
    )
    (net (code "41") (name "/OSC_OUT") (class "Default")
      (node (ref "R42") (pin "1") (pintype "passive"))
      (node (ref "U1") (pin "H1") (pinfunction "OSC_OUT_/_PH1_H1") (pintype "passive"))
    )
    (net (code "42") (name "/PA1_REFCLK") (class "Default")
      (node (ref "U1") (pin "N2") (pinfunction "PA1_N2") (pintype "passive"))
    )
    (net (code "43") (name "/PA3_ADCx-IN3") (class "Default")
      (node (ref "U1") (pin "R2") (pinfunction "PA3_R2") (pintype "passive"))
    )
    (net (code "44") (name "/PA6_ADCx-IN6") (class "Default")
      (node (ref "U1") (pin "P3") (pinfunction "PA6_P3") (pintype "passive"))
    )
    (net (code "45") (name "/PA8_MCO1") (class "Default") (node (ref "R9") (pin "1") (pintype "passive")))
    (net (code "46") (name "/PA15") (class "Default") (node (ref "R45") (pin "1") (pintype "passive")))
    (net (code "47") (name "/PB10_TIM2-CH3") (class "Default")
      (node (ref "R31") (pin "1") (pintype "passive"))
    )
    (net (code "48") (name "/PB11_TIM2-CH4") (class "Default")
      (node (ref "R34") (pin "1") (pintype "passive"))
    )
    (net (code "49") (name "/PB14_TIM12-CH1") (class "Default")
      (node (ref "U1") (pin "R14") (pinfunction "PB14_R14") (pintype "passive"))
    )
    (net (code "50") (name "/PB15_TIM12-CH2") (class "Default")
      (node (ref "U1") (pin "R15") (pinfunction "PB15_R15") (pintype "passive"))
    )
    (net (code "51") (name "/PD4") (class "Default")
      (node (ref "U1") (pin "D11") (pinfunction "PD4_D11") (pintype "passive"))
    )
    (net (code "52") (name "/PD10") (class "Default") (node (ref "R287") (pin "1") (pintype "passive")))
    (net (code "53") (name "/PD11") (class "Default")
      (node (ref "U1") (pin "N10") (pinfunction "PD11_N10") (pintype "passive"))
    )
    (net (code "54") (name "/PD12_TIM4-CH1") (class "Default")
      (node (ref "R15") (pin "1") (pintype "passive"))
    )
    (net (code "55") (name "/PD13_TIM4-CH2") (class "Default")
      (node (ref "R16") (pin "1") (pintype "passive"))
    )
    (net (code "56") (name "/PD14_TIM4-CH3") (class "Default")
      (node (ref "R17") (pin "1") (pintype "passive"))
    )
    (net (code "57") (name "/PE3") (class "Default") (node (ref "R28") (pin "1") (pintype "passive")))
    (net (code "58") (name "/PE4_SPI4-nSS") (class "Default")
      (node (ref "R29") (pin "1") (pintype "passive"))
    )
    (net (code "59") (name "/PE5_TIM9-CH1") (class "Default")
      (node (ref "U1") (pin "B1") (pinfunction "PE5_B1") (pintype "passive"))
    )
    (net (code "60") (name "/PE6_TIM9-CH2") (class "Default")
      (node (ref "U1") (pin "B2") (pinfunction "PE6_B2") (pintype "passive"))
    )
    (net (code "61") (name "/PG0") (class "Default") (node (ref "R4") (pin "1") (pintype "passive")))
    (net (code "62") (name "/PG1") (class "Default") (node (ref "R5") (pin "1") (pintype "passive")))
    (net (code "63") (name "/PG2") (class "Default") (node (ref "R6") (pin "1") (pintype "passive")))
    (net (code "64") (name "/PG3") (class "Default")
      (node (ref "U1") (pin "M12") (pinfunction "PG3_M12") (pintype "passive"))
    )
    (net (code "65") (name "/PG4") (class "Default")
      (node (ref "U1") (pin "N12") (pinfunction "PG4_N12") (pintype "passive"))
    )
    (net (code "66") (name "/PG5") (class "Default")
      (node (ref "U1") (pin "N11") (pinfunction "PG5_N11") (pintype "passive"))
    )
    (net (code "67") (name "/PG6") (class "Default")
      (node (ref "U1") (pin "J15") (pinfunction "PG6_J15") (pintype "passive"))
    )
    (net (code "68") (name "/PG7") (class "Default")
      (node (ref "U1") (pin "J14") (pinfunction "PG7_J14") (pintype "passive"))
    )
    (net (code "69") (name "/PG8_SPI6-nSS") (class "Default")
      (node (ref "R18") (pin "1") (pintype "passive"))
    )
    (net (code "70") (name "/PG9") (class "Default")
      (node (ref "U1") (pin "D9") (pinfunction "PG9_D9") (pintype "passive"))
    )
    (net (code "71") (name "/PG10") (class "Default")
      (node (ref "U1") (pin "C8") (pinfunction "PG10_C8") (pintype "passive"))
    )
    (net (code "72") (name "/PH2") (class "Default") (node (ref "R46") (pin "1") (pintype "passive")))
    (net (code "73") (name "/PH3") (class "Default")
      (node (ref "U1") (pin "J4") (pinfunction "PH3_J4") (pintype "passive"))
    )
    (net (code "74") (name "/PH4") (class "Default") (node (ref "R53") (pin "1") (pintype "passive")))
    (net (code "75") (name "/PH5_SPI5-nSS") (class "Default")
      (node (ref "R258") (pin "1") (pintype "passive"))
    )
    (net (code "76") (name "/PH9") (class "Default") (node (ref "R259") (pin "1") (pintype "passive")))
    (net (code "77") (name "/PH13") (class "Default") (node (ref "R260") (pin "1") (pintype "passive")))
    (net (code "78") (name "/PH14") (class "Default") (node (ref "R261") (pin "1") (pintype "passive")))
    (net (code "79") (name "/PH15") (class "Default") (node (ref "R262") (pin "1") (pintype "passive")))
    (net (code "80") (name "/PI8") (class "Default")
      (node (ref "U1") (pin "C2") (pinfunction "PI8_C2") (pintype "passive"))
    )
    (net (code "81") (name "/SDIO.CLK") (class "Default") (node (ref "R51") (pin "1") (pintype "passive")))
    (net (code "82") (name "/SDIO.CMD") (class "Default") (node (ref "R2") (pin "1") (pintype "passive")))
    (net (code "83") (name "/SDIO.D0") (class "Default") (node (ref "R47") (pin "1") (pintype "passive")))
    (net (code "84") (name "/SDIO.D1") (class "Default") (node (ref "R48") (pin "1") (pintype "passive")))
    (net (code "85") (name "/SDIO.D2") (class "Default") (node (ref "R49") (pin "1") (pintype "passive")))
    (net (code "86") (name "/SDIO.D3") (class "Default") (node (ref "R50") (pin "1") (pintype "passive")))
    (net (code "87") (name "/SMI.MDC") (class "Default") (node (ref "R95") (pin "1") (pintype "passive")))
    (net (code "88") (name "/SMI.MDIO") (class "Default")
      (node (ref "R52") (pin "1") (pintype "passive"))
      (node (ref "U1") (pin "P2") (pinfunction "PA2_P2") (pintype "passive"))
    )
    (net (code "89") (name "/SPI2.MISO") (class "Default")
      (node (ref "U1") (pin "C14") (pinfunction "PI2_C14") (pintype "passive"))
    )
    (net (code "90") (name "/SPI2.MOSI") (class "Default") (node (ref "R44") (pin "1") (pintype "passive")))
    (net (code "91") (name "/SPI2.SCK") (class "Default") (node (ref "R3") (pin "1") (pintype "passive")))
    (net (code "92") (name "/SPI4.MISO") (class "Default")
      (node (ref "U1") (pin "R12") (pinfunction "PE13_R12") (pintype "passive"))
    )
    (net (code "93") (name "/SPI4.MOSI") (class "Default") (node (ref "R43") (pin "1") (pintype "passive")))
    (net (code "94") (name "/SPI4.SCK") (class "Default") (node (ref "R25") (pin "1") (pintype "passive")))
    (net (code "95") (name "/SPI5.MISO") (class "Default")
      (node (ref "U1") (pin "L3") (pinfunction "PF8_L3") (pintype "passive"))
    )
    (net (code "96") (name "/SPI5.MOSI") (class "Default") (node (ref "R7") (pin "1") (pintype "passive")))
    (net (code "97") (name "/SPI5.SCK") (class "Default") (node (ref "R27") (pin "1") (pintype "passive")))
    (net (code "98") (name "/SPI6.MISO") (class "Default")
      (node (ref "U1") (pin "C7") (pinfunction "PG12_C7") (pintype "passive"))
    )
    (net (code "99") (name "/SPI6.MOSI") (class "Default") (node (ref "R23") (pin "1") (pintype "passive")))
    (net (code "100") (name "/SPI6.SCK") (class "Default") (node (ref "R19") (pin "1") (pintype "passive")))
    (net (code "101") (name "/SWD.SWCLK") (class "Default")
      (node (ref "R26") (pin "1") (pintype "passive"))
      (node (ref "U1") (pin "A14") (pinfunction "JTCK_/_SWCLK_/_PA14_A14") (pintype "passive"))
    )
    (net (code "102") (name "/SWD.SWDIO") (class "Default")
      (node (ref "R22") (pin "1") (pintype "passive"))
      (node (ref "U1") (pin "A15") (pinfunction "JTMS_/_SWDIO_/_PA13_A15") (pintype "passive"))
    )
    (net (code "103") (name "/SWD.SWO") (class "Default")
      (node (ref "R56") (pin "1") (pintype "passive"))
      (node (ref "U1") (pin "A10") (pinfunction "JTDO_/_SWO_/_PB3_A10") (pintype "passive"))
    )
    (net (code "104") (name "/UART7.RX") (class "Default")
      (node (ref "U1") (pin "R8") (pinfunction "PE7_R8") (pintype "passive"))
    )
    (net (code "105") (name "/UART7.TX") (class "Default") (node (ref "R37") (pin "1") (pintype "passive")))
    (net (code "106") (name "/UART8.RX") (class "Default")
      (node (ref "U1") (pin "A6") (pinfunction "PE0_A6") (pintype "passive"))
    )
    (net (code "107") (name "/UART8.TX") (class "Default") (node (ref "R21") (pin "1") (pintype "passive")))
    (net (code "108") (name "/USART2.RX") (class "Default")
      (node (ref "U1") (pin "B11") (pinfunction "PD6_B11") (pintype "passive"))
    )
    (net (code "109") (name "/USART2.TX") (class "Default") (node (ref "R294") (pin "1") (pintype "passive")))
    (net (code "110") (name "/USART3_RX") (class "Default")
      (node (ref "R263") (pin "1") (pintype "passive"))
      (node (ref "U1") (pin "L14") (pinfunction "PD9_L14") (pintype "passive"))
    )
    (net (code "111") (name "/USART3_TX") (class "Default")
      (node (ref "R280") (pin "1") (pintype "passive"))
      (node (ref "U1") (pin "L15") (pinfunction "PD8_L15") (pintype "passive"))
    )
    (net (code "112") (name "/USB_DFP1._N") (class "Default")
      (node (ref "U1") (pin "C15") (pinfunction "PA11_C15") (pintype "passive"))
    )
    (net (code "113") (name "/USB_DFP1._P") (class "Default")
      (node (ref "U1") (pin "B15") (pinfunction "PA12_B15") (pintype "passive"))
    )
    (net (code "114") (name "/VCAP_1") (class "Default")
      (node (ref "C2") (pin "1") (pintype "passive"))
      (node (ref "U1") (pin "L11") (pinfunction "VCAP1_L11") (pintype "passive"))
    )
    (net (code "115") (name "/VCAP_2") (class "Default")
      (node (ref "C1") (pin "1") (pintype "passive"))
      (node (ref "U1") (pin "E11") (pinfunction "VCAP2_E11") (pintype "passive"))
    )
    (net (code "125") (name "3P3") (class "Default")
      (node (ref "C10") (pin "1") (pintype "passive"))
      (node (ref "C168") (pin "1") (pintype "passive"))
      (node (ref "C4") (pin "1") (pintype "passive"))
      (node (ref "C43") (pin "1") (pintype "passive"))
      (node (ref "C45") (pin "1") (pintype "passive"))
      (node (ref "C5") (pin "1") (pintype "passive"))
      (node (ref "C6") (pin "1") (pintype "passive"))
      (node (ref "C63") (pin "1") (pintype "passive"))
      (node (ref "C64") (pin "1") (pintype "passive"))
      (node (ref "C65") (pin "1") (pintype "passive"))
      (node (ref "C66") (pin "1") (pintype "passive"))
      (node (ref "C67") (pin "1") (pintype "passive"))
      (node (ref "C68") (pin "1") (pintype "passive"))
      (node (ref "C69") (pin "1") (pintype "passive"))
      (node (ref "C8") (pin "1") (pintype "passive"))
      (node (ref "C9") (pin "1") (pintype "passive"))
      (node (ref "D1") (pin "2") (pintype "passive"))
      (node (ref "D45") (pin "2") (pintype "passive"))
      (node (ref "FB1") (pin "2") (pintype "passive"))
      (node (ref "R20") (pin "2") (pintype "passive"))
      (node (ref "R252") (pin "1") (pintype "passive"))
      (node (ref "R30") (pin "1") (pintype "passive"))
      (node (ref "R52") (pin "2") (pintype "passive"))
      (node (ref "R54") (pin "2") (pintype "passive"))
      (node (ref "S3") (pin "2") (pintype "passive"))
      (node (ref "U1") (pin "E10") (pinfunction "VDD_E10") (pintype "passive"))
      (node (ref "U1") (pin "E5") (pinfunction "PDR_ON_E5") (pintype "passive"))
      (node (ref "U1") (pin "E7") (pinfunction "VDD_E7") (pintype "passive"))
      (node (ref "U1") (pin "E8") (pinfunction "VDD_E8") (pintype "passive"))
      (node (ref "U1") (pin "E9") (pinfunction "VDD_E9") (pintype "passive"))
      (node (ref "U1") (pin "F11") (pinfunction "VDD_F11") (pintype "passive"))
      (node (ref "U1") (pin "F4") (pinfunction "VDD_F4") (pintype "passive"))
      (node (ref "U1") (pin "F5") (pinfunction "VDD_F5") (pintype "passive"))
      (node (ref "U1") (pin "G11") (pinfunction "VDD_G11") (pintype "passive"))
      (node (ref "U1") (pin "G5") (pinfunction "VDD_G5") (pintype "passive"))
      (node (ref "U1") (pin "H11") (pinfunction "VDD_H11") (pintype "passive"))
      (node (ref "U1") (pin "H5") (pinfunction "VDD_H5") (pintype "passive"))
      (node (ref "U1") (pin "J11") (pinfunction "VDD_J11") (pintype "passive"))
      (node (ref "U1") (pin "J5") (pinfunction "VDD_J5") (pintype "passive"))
      (node (ref "U1") (pin "K11") (pinfunction "VDD_K11") (pintype "passive"))
      (node (ref "U1") (pin "K5") (pinfunction "VDD_K5") (pintype "passive"))
      (node (ref "U1") (pin "L10") (pinfunction "VDD_L10") (pintype "passive"))
      (node (ref "U1") (pin "L7") (pinfunction "VDD_L7") (pintype "passive"))
      (node (ref "U1") (pin "L8") (pinfunction "VDD_L8") (pintype "passive"))
      (node (ref "U1") (pin "L9") (pinfunction "VDD_L9") (pintype "passive"))
      (node (ref "U18") (pin "6") (pinfunction "VDD_6") (pintype "passive"))
    )
    (net (code "127") (name "GND") (class "Default")
      (node (ref "C1") (pin "2") (pintype "passive"))
      (node (ref "C10") (pin "2") (pintype "passive"))
      (node (ref "C11") (pin "2") (pintype "passive"))
      (node (ref "C12") (pin "2") (pintype "passive"))
      (node (ref "C13") (pin "2") (pintype "passive"))
      (node (ref "C14") (pin "2") (pintype "passive"))
      (node (ref "C15") (pin "2") (pintype "passive"))
      (node (ref "C16") (pin "2") (pintype "passive"))
      (node (ref "C167") (pin "2") (pintype "passive"))
      (node (ref "C168") (pin "2") (pintype "passive"))
      (node (ref "C169") (pin "2") (pintype "passive"))
      (node (ref "C17") (pin "2") (pintype "passive"))
      (node (ref "C18") (pin "2") (pintype "passive"))
      (node (ref "C2") (pin "2") (pintype "passive"))
      (node (ref "C3") (pin "2") (pintype "passive"))
      (node (ref "C4") (pin "2") (pintype "passive"))
      (node (ref "C43") (pin "2") (pintype "passive"))
      (node (ref "C45") (pin "2") (pintype "passive"))
      (node (ref "C5") (pin "2") (pintype "passive"))
      (node (ref "C6") (pin "2") (pintype "passive"))
      (node (ref "C63") (pin "2") (pintype "passive"))
      (node (ref "C64") (pin "2") (pintype "passive"))
      (node (ref "C65") (pin "2") (pintype "passive"))
      (node (ref "C66") (pin "2") (pintype "passive"))
      (node (ref "C67") (pin "2") (pintype "passive"))
      (node (ref "C68") (pin "2") (pintype "passive"))
      (node (ref "C69") (pin "2") (pintype "passive"))
      (node (ref "C7") (pin "2") (pintype "passive"))
      (node (ref "C8") (pin "2") (pintype "passive"))
      (node (ref "C9") (pin "2") (pintype "passive"))
      (node (ref "D45") (pin "1") (pintype "passive"))
      (node (ref "J1") (pin "11") (pinfunction "GNDdetect_11") (pintype "passive"))
      (node (ref "J1") (pin "5") (pinfunction "GND_5") (pintype "passive"))
      (node (ref "J1") (pin "7") (pinfunction "GND_7") (pintype "passive"))
      (node (ref "R24") (pin "1") (pintype "passive"))
      (node (ref "R253") (pin "1") (pintype "passive"))
      (node (ref "R39") (pin "2") (pintype "passive"))
      (node (ref "S1") (pin "2") (pintype "passive"))
      (node (ref "S1") (pin "4") (pintype "passive"))
      (node (ref "S1") (pin "6") (pintype "passive"))
      (node (ref "S1") (pin "8") (pintype "passive"))
      (node (ref "S2") (pin "1") (pintype "passive"))
      (node (ref "TP52") (pin "1") (pintype "passive"))
      (node (ref "U1") (pin "F10") (pinfunction "VSS_F10") (pintype "passive"))
      (node (ref "U1") (pin "F2") (pinfunction "VSS_F2") (pintype "passive"))
      (node (ref "U1") (pin "F6") (pinfunction "VSS_F6") (pintype "passive"))
      (node (ref "U1") (pin "F7") (pinfunction "VSS_F7") (pintype "passive"))
      (node (ref "U1") (pin "F8") (pinfunction "VSS_F8") (pintype "passive"))
      (node (ref "U1") (pin "F9") (pinfunction "VSS_F9") (pintype "passive"))
      (node (ref "U1") (pin "G10") (pinfunction "VSS_G10") (pintype "passive"))
      (node (ref "U1") (pin "G6") (pinfunction "VSS_G6") (pintype "passive"))
      (node (ref "U1") (pin "H10") (pinfunction "VSS_H10") (pintype "passive"))
      (node (ref "U1") (pin "H6") (pinfunction "VSS_H6") (pintype "passive"))
      (node (ref "U1") (pin "J10") (pinfunction "VSS_J10") (pintype "passive"))
      (node (ref "U1") (pin "J6") (pinfunction "VSS_J6") (pintype "passive"))
      (node (ref "U1") (pin "K10") (pinfunction "VSS_K10") (pintype "passive"))
      (node (ref "U1") (pin "K6") (pinfunction "VSS_K6") (pintype "passive"))
      (node (ref "U1") (pin "K7") (pinfunction "VSS_K7") (pintype "passive"))
      (node (ref "U1") (pin "K8") (pinfunction "VSS_K8") (pintype "passive"))
      (node (ref "U1") (pin "K9") (pinfunction "VSS_K9") (pintype "passive"))
      (node (ref "U1") (pin "L5") (pinfunction "BYPASS_REG_L5") (pintype "passive"))
      (node (ref "U1") (pin "L6") (pinfunction "VSS_L6") (pintype "passive"))
      (node (ref "U1") (pin "M1") (pinfunction "VSSA_M1") (pintype "passive"))
      (node (ref "U1") (pin "N1") (pinfunction "VREFM_N1") (pintype "passive"))
      (node (ref "U18") (pin "2") (pinfunction "GND_2") (pintype "passive"))
      (node (ref "U18") (pin "3") (pinfunction "GND_3") (pintype "passive"))
      (node (ref "U18") (pin "5") (pinfunction "GND_5") (pintype "passive"))
    )
    (net (code "128") (name "Net-(C13-Pad1)") (class "Default")
      (node (ref "C13") (pin "1") (pintype "passive"))
      (node (ref "R11") (pin "1") (pintype "passive"))
    )
    (net (code "129") (name "Net-(C15-Pad1)") (class "Default")
      (node (ref "C15") (pin "1") (pintype "passive"))
      (node (ref "R42") (pin "2") (pintype "passive"))
      (node (ref "X1") (pin "1") (pinfunction "1_1") (pintype "passive"))
    )
    (net (code "130") (name "Net-(C18-Pad1)") (class "Default")
      (node (ref "C18") (pin "1") (pintype "passive"))
      (node (ref "R55") (pin "2") (pintype "passive"))
      (node (ref "X2") (pin "1") (pinfunction "1_1") (pintype "passive"))
    )
    (net (code "131") (name "Net-(D1-Pad1)") (class "Default")
      (node (ref "D1") (pin "1") (pintype "passive"))
      (node (ref "R14") (pin "1") (pintype "passive"))
    )
    (net (code "132") (name "Net-(D1-Pad3)") (class "Default")
      (node (ref "D1") (pin "3") (pintype "passive"))
      (node (ref "R13") (pin "1") (pintype "passive"))
    )
    (net (code "133") (name "Net-(D1-Pad4)") (class "Default")
      (node (ref "D1") (pin "4") (pintype "passive"))
      (node (ref "R10") (pin "1") (pintype "passive"))
    )
    (net (code "134") (name "Net-(J1-T_VCC)") (class "Default")
      (node (ref "J1") (pin "3") (pinfunction "T_VCC_3") (pintype "passive"))
      (node (ref "R20") (pin "1") (pintype "passive"))
    )
    (net (code "135") (name "Net-(R254-Pad2)") (class "Default")
      (node (ref "R254") (pin "2") (pintype "passive"))
      (node (ref "TP51") (pin "1") (pintype "passive"))
    )
    (net (code "136") (name "Net-(U1A-JTDI_{slash}_PA15)") (class "Default")
      (node (ref "R45") (pin "2") (pintype "passive"))
      (node (ref "U1") (pin "A13") (pinfunction "JTDI_/_PA15_A13") (pintype "passive"))
    )
    (net (code "137") (name "Net-(U1A-PA4)") (class "Default")
      (node (ref "R8") (pin "1") (pintype "passive"))
      (node (ref "U1") (pin "N4") (pinfunction "PA4_N4") (pintype "passive"))
    )
    (net (code "138") (name "Net-(U1A-PA5)") (class "Default")
      (node (ref "R12") (pin "1") (pintype "passive"))
      (node (ref "U1") (pin "P4") (pinfunction "PA5_P4") (pintype "passive"))
    )
    (net (code "139") (name "Net-(U1A-PA8)") (class "Default")
      (node (ref "R9") (pin "2") (pintype "passive"))
      (node (ref "U1") (pin "F15") (pinfunction "PA8_F15") (pintype "passive"))
    )
    (net (code "140") (name "Net-(U1B-BOOT1_{slash}_PB2)") (class "Default")
      (node (ref "R24") (pin "2") (pintype "passive"))
      (node (ref "U1") (pin "M5") (pinfunction "BOOT1_/_PB2_M5") (pintype "passive"))
    )
    (net (code "141") (name "Net-(U1B-PB0)") (class "Default")
      (node (ref "C167") (pin "1") (pintype "passive"))
      (node (ref "R251") (pin "2") (pintype "passive"))
      (node (ref "U1") (pin "R5") (pinfunction "PB0_R5") (pintype "passive"))
    )
    (net (code "142") (name "Net-(U1B-PB1)") (class "Default")
      (node (ref "C169") (pin "1") (pintype "passive"))
      (node (ref "D45") (pin "3") (pintype "passive"))
      (node (ref "R254") (pin "1") (pintype "passive"))
      (node (ref "U1") (pin "R4") (pinfunction "PB1_R4") (pintype "passive"))
    )
    (net (code "143") (name "Net-(U1B-PB6)") (class "Default")
      (node (ref "R33") (pin "2") (pintype "passive"))
      (node (ref "U1") (pin "B6") (pinfunction "PB6_B6") (pintype "passive"))
    )
    (net (code "144") (name "Net-(U1B-PB7)") (class "Default")
      (node (ref "R35") (pin "2") (pintype "passive"))
      (node (ref "U1") (pin "B5") (pinfunction "PB7_B5") (pintype "passive"))
    )
    (net (code "145") (name "Net-(U1B-PB8)") (class "Default")
      (node (ref "R36") (pin "2") (pintype "passive"))
      (node (ref "U1") (pin "A7") (pinfunction "PB8_A7") (pintype "passive"))
    )
    (net (code "146") (name "Net-(U1B-PB10)") (class "Default")
      (node (ref "R31") (pin "2") (pintype "passive"))
      (node (ref "U1") (pin "P12") (pinfunction "PB10_P12") (pintype "passive"))
    )
    (net (code "147") (name "Net-(U1B-PB11)") (class "Default")
      (node (ref "R34") (pin "2") (pintype "passive"))
      (node (ref "U1") (pin "R13") (pinfunction "PB11_R13") (pintype "passive"))
    )
    (net (code "148") (name "Net-(U1B-PB12)") (class "Default")
      (node (ref "R40") (pin "2") (pintype "passive"))
      (node (ref "U1") (pin "L13") (pinfunction "PB12_L13") (pintype "passive"))
    )
    (net (code "149") (name "Net-(U1B-PB13)") (class "Default")
      (node (ref "R41") (pin "2") (pintype "passive"))
      (node (ref "U1") (pin "K14") (pinfunction "PB13_K14") (pintype "passive"))
    )
    (net (code "150") (name "Net-(U1C-PC1)") (class "Default")
      (node (ref "R95") (pin "2") (pintype "passive"))
      (node (ref "U1") (pin "M3") (pinfunction "PC1_M3") (pintype "passive"))
    )
    (net (code "151") (name "Net-(U1C-PC8)") (class "Default")
      (node (ref "R47") (pin "2") (pintype "passive"))
      (node (ref "U1") (pin "G14") (pinfunction "PC8_G14") (pintype "passive"))
    )
    (net (code "152") (name "Net-(U1C-PC9)") (class "Default")
      (node (ref "R48") (pin "2") (pintype "passive"))
      (node (ref "U1") (pin "F14") (pinfunction "PC9_F14") (pintype "passive"))
    )
    (net (code "153") (name "Net-(U1C-PC10)") (class "Default")
      (node (ref "R49") (pin "2") (pintype "passive"))
      (node (ref "U1") (pin "B14") (pinfunction "PC10_B14") (pintype "passive"))
    )
    (net (code "154") (name "Net-(U1C-PC11)") (class "Default")
      (node (ref "R50") (pin "2") (pintype "passive"))
      (node (ref "U1") (pin "B13") (pinfunction "PC11_B13") (pintype "passive"))
    )
    (net (code "155") (name "Net-(U1C-PC12)") (class "Default")
      (node (ref "R51") (pin "2") (pintype "passive"))
      (node (ref "U1") (pin "A12") (pinfunction "PC12_A12") (pintype "passive"))
    )
    (net (code "156") (name "Net-(U1C-PC14_{slash}_OSC32_IN)") (class "Default")
      (node (ref "C17") (pin "1") (pintype "passive"))
      (node (ref "U1") (pin "E1") (pinfunction "PC14_/_OSC32_IN_E1") (pintype "passive"))
      (node (ref "X2") (pin "2") (pinfunction "2_2") (pintype "passive"))
    )
    (net (code "157") (name "Net-(U1C-PC15_{slash}_OSC32_OUT)") (class "Default")
      (node (ref "R55") (pin "1") (pintype "passive"))
      (node (ref "U1") (pin "F1") (pinfunction "PC15_/_OSC32_OUT_F1") (pintype "passive"))
    )
    (net (code "158") (name "Net-(U1D-PD1)") (class "Default")
      (node (ref "R1") (pin "2") (pintype "passive"))
      (node (ref "U1") (pin "C12") (pinfunction "PD1_C12") (pintype "passive"))
    )
    (net (code "159") (name "Net-(U1D-PD2)") (class "Default")
      (node (ref "R2") (pin "2") (pintype "passive"))
      (node (ref "U1") (pin "D12") (pinfunction "PD2_D12") (pintype "passive"))
    )
    (net (code "160") (name "Net-(U1D-PD5)") (class "Default")
      (node (ref "R294") (pin "2") (pintype "passive"))
      (node (ref "U1") (pin "C10") (pinfunction "PD5_C10") (pintype "passive"))
    )
    (net (code "161") (name "Net-(U1D-PD10)") (class "Default")
      (node (ref "R287") (pin "2") (pintype "passive"))
      (node (ref "U1") (pin "K15") (pinfunction "PD10_K15") (pintype "passive"))
    )
    (net (code "162") (name "Net-(U1D-PD12)") (class "Default")
      (node (ref "R15") (pin "2") (pintype "passive"))
      (node (ref "U1") (pin "M10") (pinfunction "PD12_M10") (pintype "passive"))
    )
    (net (code "163") (name "Net-(U1D-PD13)") (class "Default")
      (node (ref "R16") (pin "2") (pintype "passive"))
      (node (ref "U1") (pin "M11") (pinfunction "PD13_M11") (pintype "passive"))
    )
    (net (code "164") (name "Net-(U1D-PD14)") (class "Default")
      (node (ref "R17") (pin "2") (pintype "passive"))
      (node (ref "U1") (pin "L12") (pinfunction "PD14_L12") (pintype "passive"))
    )
    (net (code "165") (name "Net-(U1E-PE1)") (class "Default")
      (node (ref "R21") (pin "2") (pintype "passive"))
      (node (ref "U1") (pin "A5") (pinfunction "PE1_A5") (pintype "passive"))
    )
    (net (code "166") (name "Net-(U1E-PE2)") (class "Default")
      (node (ref "R25") (pin "2") (pintype "passive"))
      (node (ref "U1") (pin "A3") (pinfunction "PE2_A3") (pintype "passive"))
    )
    (net (code "167") (name "Net-(U1E-PE3)") (class "Default")
      (node (ref "R28") (pin "2") (pintype "passive"))
      (node (ref "U1") (pin "A2") (pinfunction "PE3_A2") (pintype "passive"))
    )
    (net (code "168") (name "Net-(U1E-PE4)") (class "Default")
      (node (ref "R29") (pin "2") (pintype "passive"))
      (node (ref "U1") (pin "A1") (pinfunction "PE4_A1") (pintype "passive"))
    )
    (net (code "169") (name "Net-(U1E-PE8)") (class "Default")
      (node (ref "R37") (pin "2") (pintype "passive"))
      (node (ref "U1") (pin "N9") (pinfunction "PE8_N9") (pintype "passive"))
    )
    (net (code "170") (name "Net-(U1E-PE14)") (class "Default")
      (node (ref "R43") (pin "2") (pintype "passive"))
      (node (ref "U1") (pin "P11") (pinfunction "PE14_P11") (pintype "passive"))
    )
    (net (code "171") (name "Net-(U1F-PF7)") (class "Default")
      (node (ref "R27") (pin "2") (pintype "passive"))
      (node (ref "U1") (pin "K1") (pinfunction "PF7_K1") (pintype "passive"))
    )
    (net (code "172") (name "Net-(U1F-PF9)") (class "Default")
      (node (ref "R7") (pin "2") (pintype "passive"))
      (node (ref "U1") (pin "L2") (pinfunction "PF9_L2") (pintype "passive"))
    )
    (net (code "173") (name "Net-(U1G-PG0)") (class "Default")
      (node (ref "R4") (pin "2") (pintype "passive"))
      (node (ref "U1") (pin "N7") (pinfunction "PG0_N7") (pintype "passive"))
    )
    (net (code "174") (name "Net-(U1G-PG1)") (class "Default")
      (node (ref "R5") (pin "2") (pintype "passive"))
      (node (ref "U1") (pin "M7") (pinfunction "PG1_M7") (pintype "passive"))
    )
    (net (code "175") (name "Net-(U1G-PG2)") (class "Default")
      (node (ref "R6") (pin "2") (pintype "passive"))
      (node (ref "U1") (pin "M13") (pinfunction "PG2_M13") (pintype "passive"))
    )
    (net (code "176") (name "Net-(U1G-PG8)") (class "Default")
      (node (ref "R18") (pin "2") (pintype "passive"))
      (node (ref "U1") (pin "H14") (pinfunction "PG8_H14") (pintype "passive"))
    )
    (net (code "177") (name "Net-(U1G-PG11)") (class "Default")
      (node (ref "R38") (pin "2") (pintype "passive"))
      (node (ref "U1") (pin "B8") (pinfunction "PG11_B8") (pintype "passive"))
    )
    (net (code "178") (name "Net-(U1G-PG13)") (class "Default")
      (node (ref "R19") (pin "2") (pintype "passive"))
      (node (ref "U1") (pin "B3") (pinfunction "PG13_B3") (pintype "passive"))
    )
    (net (code "179") (name "Net-(U1G-PG14)") (class "Default")
      (node (ref "R23") (pin "2") (pintype "passive"))
      (node (ref "U1") (pin "A4") (pinfunction "PG14_A4") (pintype "passive"))
    )
    (net (code "180") (name "Net-(U1H-PH2)") (class "Default")
      (node (ref "R46") (pin "2") (pintype "passive"))
      (node (ref "U1") (pin "K4") (pinfunction "PH2_K4") (pintype "passive"))
    )
    (net (code "181") (name "Net-(U1H-PH4)") (class "Default")
      (node (ref "R53") (pin "2") (pintype "passive"))
      (node (ref "U1") (pin "H4") (pinfunction "PH4_H4") (pintype "passive"))
    )
    (net (code "182") (name "Net-(U1H-PH5)") (class "Default")
      (node (ref "R258") (pin "2") (pintype "passive"))
      (node (ref "U1") (pin "J3") (pinfunction "PH5_J3") (pintype "passive"))
    )
    (net (code "183") (name "Net-(U1H-PH9)") (class "Default")
      (node (ref "R259") (pin "2") (pintype "passive"))
      (node (ref "U1") (pin "N14") (pinfunction "PH9_N14") (pintype "passive"))
    )
    (net (code "184") (name "Net-(U1H-PH13)") (class "Default")
      (node (ref "R260") (pin "2") (pintype "passive"))
      (node (ref "U1") (pin "E12") (pinfunction "PH13_E12") (pintype "passive"))
    )
    (net (code "185") (name "Net-(U1H-PH14)") (class "Default")
      (node (ref "R261") (pin "2") (pintype "passive"))
      (node (ref "U1") (pin "E13") (pinfunction "PH14_E13") (pintype "passive"))
    )
    (net (code "186") (name "Net-(U1H-PH15)") (class "Default")
      (node (ref "R262") (pin "2") (pintype "passive"))
      (node (ref "U1") (pin "D13") (pinfunction "PH15_D13") (pintype "passive"))
    )
    (net (code "187") (name "Net-(U1I-PI1)") (class "Default")
      (node (ref "R3") (pin "2") (pintype "passive"))
      (node (ref "U1") (pin "D14") (pinfunction "PI1_D14") (pintype "passive"))
    )
    (net (code "188") (name "Net-(U1I-PI3)") (class "Default")
      (node (ref "R44") (pin "2") (pintype "passive"))
      (node (ref "U1") (pin "C13") (pinfunction "PI3_C13") (pintype "passive"))
    )
    (net (code "189") (name "Net-(U18-OUT)") (class "Default")
      (node (ref "R251") (pin "1") (pintype "passive"))
      (node (ref "R253") (pin "2") (pintype "passive"))
      (node (ref "U18") (pin "1") (pinfunction "OUT_1") (pintype "passive"))
    )
    (net (code "190") (name "Net-(U18-nSHDN)") (class "Default")
      (node (ref "R252") (pin "2") (pintype "passive"))
      (node (ref "U18") (pin "4") (pinfunction "nSHDN_4") (pintype "passive"))
    )
    (net (code "191") (name "VBAT") (class "Default")
      (node (ref "C7") (pin "1") (pintype "passive"))
      (node (ref "U1") (pin "C1") (pinfunction "VBAT_C1") (pintype "passive"))
    )
    (net (code "192") (name "unconnected-(J1-NC-Pad1)") (class "Default")
      (node (ref "J1") (pin "1") (pinfunction "NC_1") (pintype "passive"))
    )
    (net (code "193") (name "unconnected-(J1-NC-Pad2)") (class "Default")
      (node (ref "J1") (pin "2") (pinfunction "NC_2") (pintype "passive"))
    )
    (net (code "194") (name "unconnected-(J1-T_JRCLK{slash}NC-Pad9)") (class "Default")
      (node (ref "J1") (pin "9") (pinfunction "T_JRCLK/NC_9") (pintype "passive"))
    )
    (net (code "195") (name "unconnected-(J1-T_JTDI{slash}NC-Pad10)") (class "Default")
      (node (ref "J1") (pin "10") (pinfunction "T_JTDI/NC_10") (pintype "passive"))
    )
    (net (code "196") (name "unconnected-(U1A-PA0_{slash}_WKUP-PadN3)") (class "Default")
      (node (ref "U1") (pin "N3") (pinfunction "PA0_/_WKUP_N3") (pintype "passive"))
    )
    (net (code "197") (name "unconnected-(U1A-PA9-PadE15)") (class "Default")
      (node (ref "U1") (pin "E15") (pinfunction "PA9_E15") (pintype "passive"))
    )
    (net (code "198") (name "unconnected-(U1A-PA10-PadD15)") (class "Default")
      (node (ref "U1") (pin "D15") (pinfunction "PA10_D15") (pintype "passive"))
    )
    (net (code "199") (name "unconnected-(U1B-PB9-PadB4)") (class "Default")
      (node (ref "U1") (pin "B4") (pinfunction "PB9_B4") (pintype "passive"))
    )
    (net (code "200") (name "unconnected-(U1B-nJTRST_{slash}_PB4-PadA9)") (class "Default")
      (node (ref "U1") (pin "A9") (pinfunction "nJTRST_/_PB4_A9") (pintype "passive"))
    )
    (net (code "201") (name "unconnected-(U1C-PC0-PadM2)") (class "Default")
      (node (ref "U1") (pin "M2") (pinfunction "PC0_M2") (pintype "passive"))
    )
    (net (code "202") (name "unconnected-(U1C-PC2-PadM4)") (class "Default")
      (node (ref "U1") (pin "M4") (pinfunction "PC2_M4") (pintype "passive"))
    )
    (net (code "203") (name "unconnected-(U1C-PC3-PadL4)") (class "Default")
      (node (ref "U1") (pin "L4") (pinfunction "PC3_L4") (pintype "passive"))
    )
    (net (code "204") (name "unconnected-(U1C-PC6-PadH15)") (class "Default")
      (node (ref "U1") (pin "H15") (pinfunction "PC6_H15") (pintype "passive"))
    )
    (net (code "205") (name "unconnected-(U1C-PC7-PadG15)") (class "Default")
      (node (ref "U1") (pin "G15") (pinfunction "PC7_G15") (pintype "passive"))
    )
    (net (code "206") (name "unconnected-(U1C-PC13-PadD1)") (class "Default")
      (node (ref "U1") (pin "D1") (pinfunction "PC13_D1") (pintype "passive"))
    )
    (net (code "207") (name "unconnected-(U1D-PD3-PadC11)") (class "Default")
      (node (ref "U1") (pin "C11") (pinfunction "PD3_C11") (pintype "passive"))
    )
    (net (code "208") (name "unconnected-(U1D-PD7-PadA11)") (class "Default")
      (node (ref "U1") (pin "A11") (pinfunction "PD7_A11") (pintype "passive"))
    )
    (net (code "209") (name "unconnected-(U1D-PD15-PadK13)") (class "Default")
      (node (ref "U1") (pin "K13") (pinfunction "PD15_K13") (pintype "passive"))
    )
    (net (code "210") (name "unconnected-(U1E-PE9-PadP9)") (class "Default")
      (node (ref "U1") (pin "P9") (pinfunction "PE9_P9") (pintype "passive"))
    )
    (net (code "211") (name "unconnected-(U1E-PE10-PadR9)") (class "Default")
      (node (ref "U1") (pin "R9") (pinfunction "PE10_R9") (pintype "passive"))
    )
    (net (code "212") (name "unconnected-(U1E-PE11-PadP10)") (class "Default")
      (node (ref "U1") (pin "P10") (pinfunction "PE11_P10") (pintype "passive"))
    )
    (net (code "213") (name "unconnected-(U1E-PE12-PadR10)") (class "Default")
      (node (ref "U1") (pin "R10") (pinfunction "PE12_R10") (pintype "passive"))
    )
    (net (code "214") (name "unconnected-(U1E-PE15-PadR11)") (class "Default")
      (node (ref "U1") (pin "R11") (pinfunction "PE15_R11") (pintype "passive"))
    )
    (net (code "215") (name "unconnected-(U1F-PF0-PadD2)") (class "Default")
      (node (ref "U1") (pin "D2") (pinfunction "PF0_D2") (pintype "passive"))
    )
    (net (code "216") (name "unconnected-(U1F-PF1-PadE2)") (class "Default")
      (node (ref "U1") (pin "E2") (pinfunction "PF1_E2") (pintype "passive"))
    )
    (net (code "217") (name "unconnected-(U1F-PF2-PadG2)") (class "Default")
      (node (ref "U1") (pin "G2") (pinfunction "PF2_G2") (pintype "passive"))
    )
    (net (code "218") (name "unconnected-(U1F-PF3-PadH2)") (class "Default")
      (node (ref "U1") (pin "H2") (pinfunction "PF3_H2") (pintype "passive"))
    )
    (net (code "219") (name "unconnected-(U1F-PF4-PadJ2)") (class "Default")
      (node (ref "U1") (pin "J2") (pinfunction "PF4_J2") (pintype "passive"))
    )
    (net (code "220") (name "unconnected-(U1F-PF5-PadK3)") (class "Default")
      (node (ref "U1") (pin "K3") (pinfunction "PF5_K3") (pintype "passive"))
    )
    (net (code "221") (name "unconnected-(U1F-PF6-PadK2)") (class "Default")
      (node (ref "U1") (pin "K2") (pinfunction "PF6_K2") (pintype "passive"))
    )
    (net (code "222") (name "unconnected-(U1F-PF10-PadL1)") (class "Default")
      (node (ref "U1") (pin "L1") (pinfunction "PF10_L1") (pintype "passive"))
    )
    (net (code "223") (name "unconnected-(U1F-PF11-PadP8)") (class "Default")
      (node (ref "U1") (pin "P8") (pinfunction "PF11_P8") (pintype "passive"))
    )
    (net (code "224") (name "unconnected-(U1G-PG15-PadB7)") (class "Default")
      (node (ref "U1") (pin "B7") (pinfunction "PG15_B7") (pintype "passive"))
    )
    (net (code "225") (name "unconnected-(U1H-PH6-PadP13)") (class "Default")
      (node (ref "U1") (pin "P13") (pinfunction "PH6_P13") (pintype "passive"))
    )
    (net (code "226") (name "unconnected-(U1H-PH7-PadN13)") (class "Default")
      (node (ref "U1") (pin "N13") (pinfunction "PH7_N13") (pintype "passive"))
    )
    (net (code "227") (name "unconnected-(U1H-PH8-PadP14)") (class "Default")
      (node (ref "U1") (pin "P14") (pinfunction "PH8_P14") (pintype "passive"))
    )
    (net (code "228") (name "unconnected-(U1I-PI0-PadE14)") (class "Default")
      (node (ref "U1") (pin "E14") (pinfunction "PI0_E14") (pintype "passive"))
    )
    (net (code "229") (name "unconnected-(U1I-PI4-PadC3)") (class "Default")
      (node (ref "U1") (pin "C3") (pinfunction "PI4_C3") (pintype "passive"))
    )
    (net (code "230") (name "unconnected-(U1I-PI5-PadD3)") (class "Default")
      (node (ref "U1") (pin "D3") (pinfunction "PI5_D3") (pintype "passive"))
    )
    (net (code "231") (name "unconnected-(U1I-PI6-PadD6)") (class "Default")
      (node (ref "U1") (pin "D6") (pinfunction "PI6_D6") (pintype "passive"))
    )
    (net (code "232") (name "unconnected-(U1I-PI7-PadD4)") (class "Default")
      (node (ref "U1") (pin "D4") (pinfunction "PI7_D4") (pintype "passive"))
    )
    (net (code "233") (name "unconnected-(U1I-PI9-PadE4)") (class "Default")
      (node (ref "U1") (pin "E4") (pinfunction "PI9_E4") (pintype "passive"))
    )
    (net (code "234") (name "unconnected-(U1I-PI10-PadD5)") (class "Default")
      (node (ref "U1") (pin "D5") (pinfunction "PI10_D5") (pintype "passive"))
    )
    (net (code "235") (name "unconnected-(U1I-PI11-PadF3)") (class "Default")
      (node (ref "U1") (pin "F3") (pinfunction "PI11_F3") (pintype "passive"))
    )
    (net (code "236") (name "unconnected-(U1I-PI12-PadE3)") (class "Default")
      (node (ref "U1") (pin "E3") (pinfunction "PI12_E3") (pintype "passive"))
    )
    (net (code "237") (name "unconnected-(U1I-PI13-PadG3)") (class "Default")
      (node (ref "U1") (pin "G3") (pinfunction "PI13_G3") (pintype "passive"))
    )
    (net (code "238") (name "unconnected-(U1I-PI14-PadH3)") (class "Default")
      (node (ref "U1") (pin "H3") (pinfunction "PI14_H3") (pintype "passive"))
    )
    (net (code "239") (name "unconnected-(U1I-PI15-PadG4)") (class "Default")
      (node (ref "U1") (pin "G4") (pinfunction "PI15_G4") (pintype "passive"))
    )
    (net (code "240") (name "unconnected-(U1J-PJ0-PadR6)") (class "Default")
      (node (ref "U1") (pin "R6") (pinfunction "PJ0_R6") (pintype "passive"))
    )
    (net (code "241") (name "unconnected-(U1J-PJ1-PadR7)") (class "Default")
      (node (ref "U1") (pin "R7") (pinfunction "PJ1_R7") (pintype "passive"))
    )
    (net (code "242") (name "unconnected-(U1J-PJ2-PadP7)") (class "Default")
      (node (ref "U1") (pin "P7") (pinfunction "PJ2_P7") (pintype "passive"))
    )
    (net (code "243") (name "unconnected-(U1J-PJ3-PadN8)") (class "Default")
      (node (ref "U1") (pin "N8") (pinfunction "PJ3_N8") (pintype "passive"))
    )
    (net (code "244") (name "unconnected-(U1J-PJ4-PadM9)") (class "Default")
      (node (ref "U1") (pin "M9") (pinfunction "PJ4_M9") (pintype "passive"))
    )
    (net (code "245") (name "unconnected-(U1J-PJ5-PadM14)") (class "Default")
      (node (ref "U1") (pin "M14") (pinfunction "PJ5_M14") (pintype "passive"))
    )
    (net (code "246") (name "unconnected-(U1J-PJ6-PadK12)") (class "Default")
      (node (ref "U1") (pin "K12") (pinfunction "PJ6_K12") (pintype "passive"))
    )
    (net (code "247") (name "unconnected-(U1J-PJ7-PadJ12)") (class "Default")
      (node (ref "U1") (pin "J12") (pinfunction "PJ7_J12") (pintype "passive"))
    )
    (net (code "248") (name "unconnected-(U1J-PJ8-PadH12)") (class "Default")
      (node (ref "U1") (pin "H12") (pinfunction "PJ8_H12") (pintype "passive"))
    )
    (net (code "249") (name "unconnected-(U1J-PJ9-PadJ13)") (class "Default")
      (node (ref "U1") (pin "J13") (pinfunction "PJ9_J13") (pintype "passive"))
    )
    (net (code "250") (name "unconnected-(U1J-PJ10-PadH13)") (class "Default")
      (node (ref "U1") (pin "H13") (pinfunction "PJ10_H13") (pintype "passive"))
    )
    (net (code "251") (name "unconnected-(U1J-PJ11-PadG12)") (class "Default")
      (node (ref "U1") (pin "G12") (pinfunction "PJ11_G12") (pintype "passive"))
    )
    (net (code "252") (name "unconnected-(U1J-PJ12-PadB10)") (class "Default")
      (node (ref "U1") (pin "B10") (pinfunction "PJ12_B10") (pintype "passive"))
    )
    (net (code "253") (name "unconnected-(U1J-PJ13-PadB9)") (class "Default")
      (node (ref "U1") (pin "B9") (pinfunction "PJ13_B9") (pintype "passive"))
    )
    (net (code "254") (name "unconnected-(U1J-PJ14-PadC9)") (class "Default")
      (node (ref "U1") (pin "C9") (pinfunction "PJ14_C9") (pintype "passive"))
    )
    (net (code "255") (name "unconnected-(U1J-PJ15-PadD10)") (class "Default")
      (node (ref "U1") (pin "D10") (pinfunction "PJ15_D10") (pintype "passive"))
    )
    (net (code "256") (name "unconnected-(U1K-PK0-PadG13)") (class "Default")
      (node (ref "U1") (pin "G13") (pinfunction "PK0_G13") (pintype "passive"))
    )
    (net (code "257") (name "unconnected-(U1K-PK1-PadF12)") (class "Default")
      (node (ref "U1") (pin "F12") (pinfunction "PK1_F12") (pintype "passive"))
    )
    (net (code "258") (name "unconnected-(U1K-PK2-PadF13)") (class "Default")
      (node (ref "U1") (pin "F13") (pinfunction "PK2_F13") (pintype "passive"))
    )
    (net (code "259") (name "unconnected-(U1K-PK3-PadD8)") (class "Default")
      (node (ref "U1") (pin "D8") (pinfunction "PK3_D8") (pintype "passive"))
    )
    (net (code "260") (name "unconnected-(U1K-PK4-PadD7)") (class "Default")
      (node (ref "U1") (pin "D7") (pinfunction "PK4_D7") (pintype "passive"))
    )
    (net (code "261") (name "unconnected-(U1K-PK5-PadC6)") (class "Default")
      (node (ref "U1") (pin "C6") (pinfunction "PK5_C6") (pintype "passive"))
    )
    (net (code "262") (name "unconnected-(U1K-PK6-PadC5)") (class "Default")
      (node (ref "U1") (pin "C5") (pinfunction "PK6_C5") (pintype "passive"))
    )
    (net (code "263") (name "unconnected-(U1K-PK7-PadC4)") (class "Default")
      (node (ref "U1") (pin "C4") (pinfunction "PK7_C4") (pintype "passive"))
    )
  )
)
